# DUE3DOM_MINI_23052016-1301.net
KiCad netlist of a schematic drawn in EAGLE
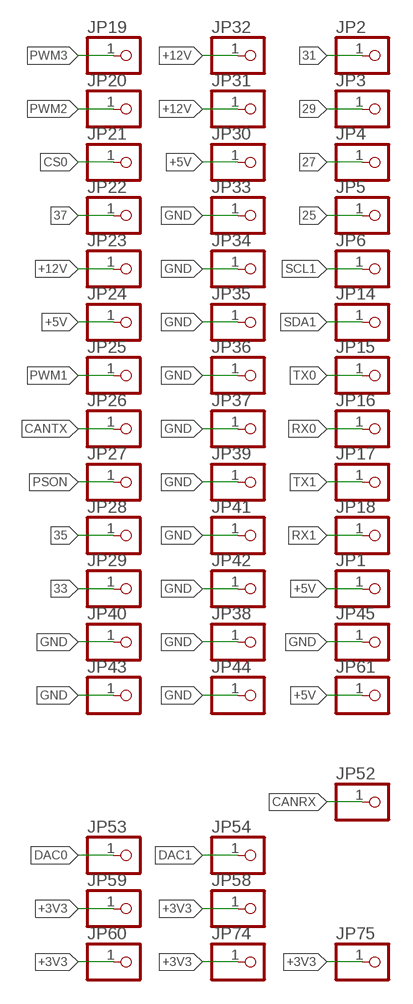
[diagram p0: schematic, sheet 1, part 1 of 3]
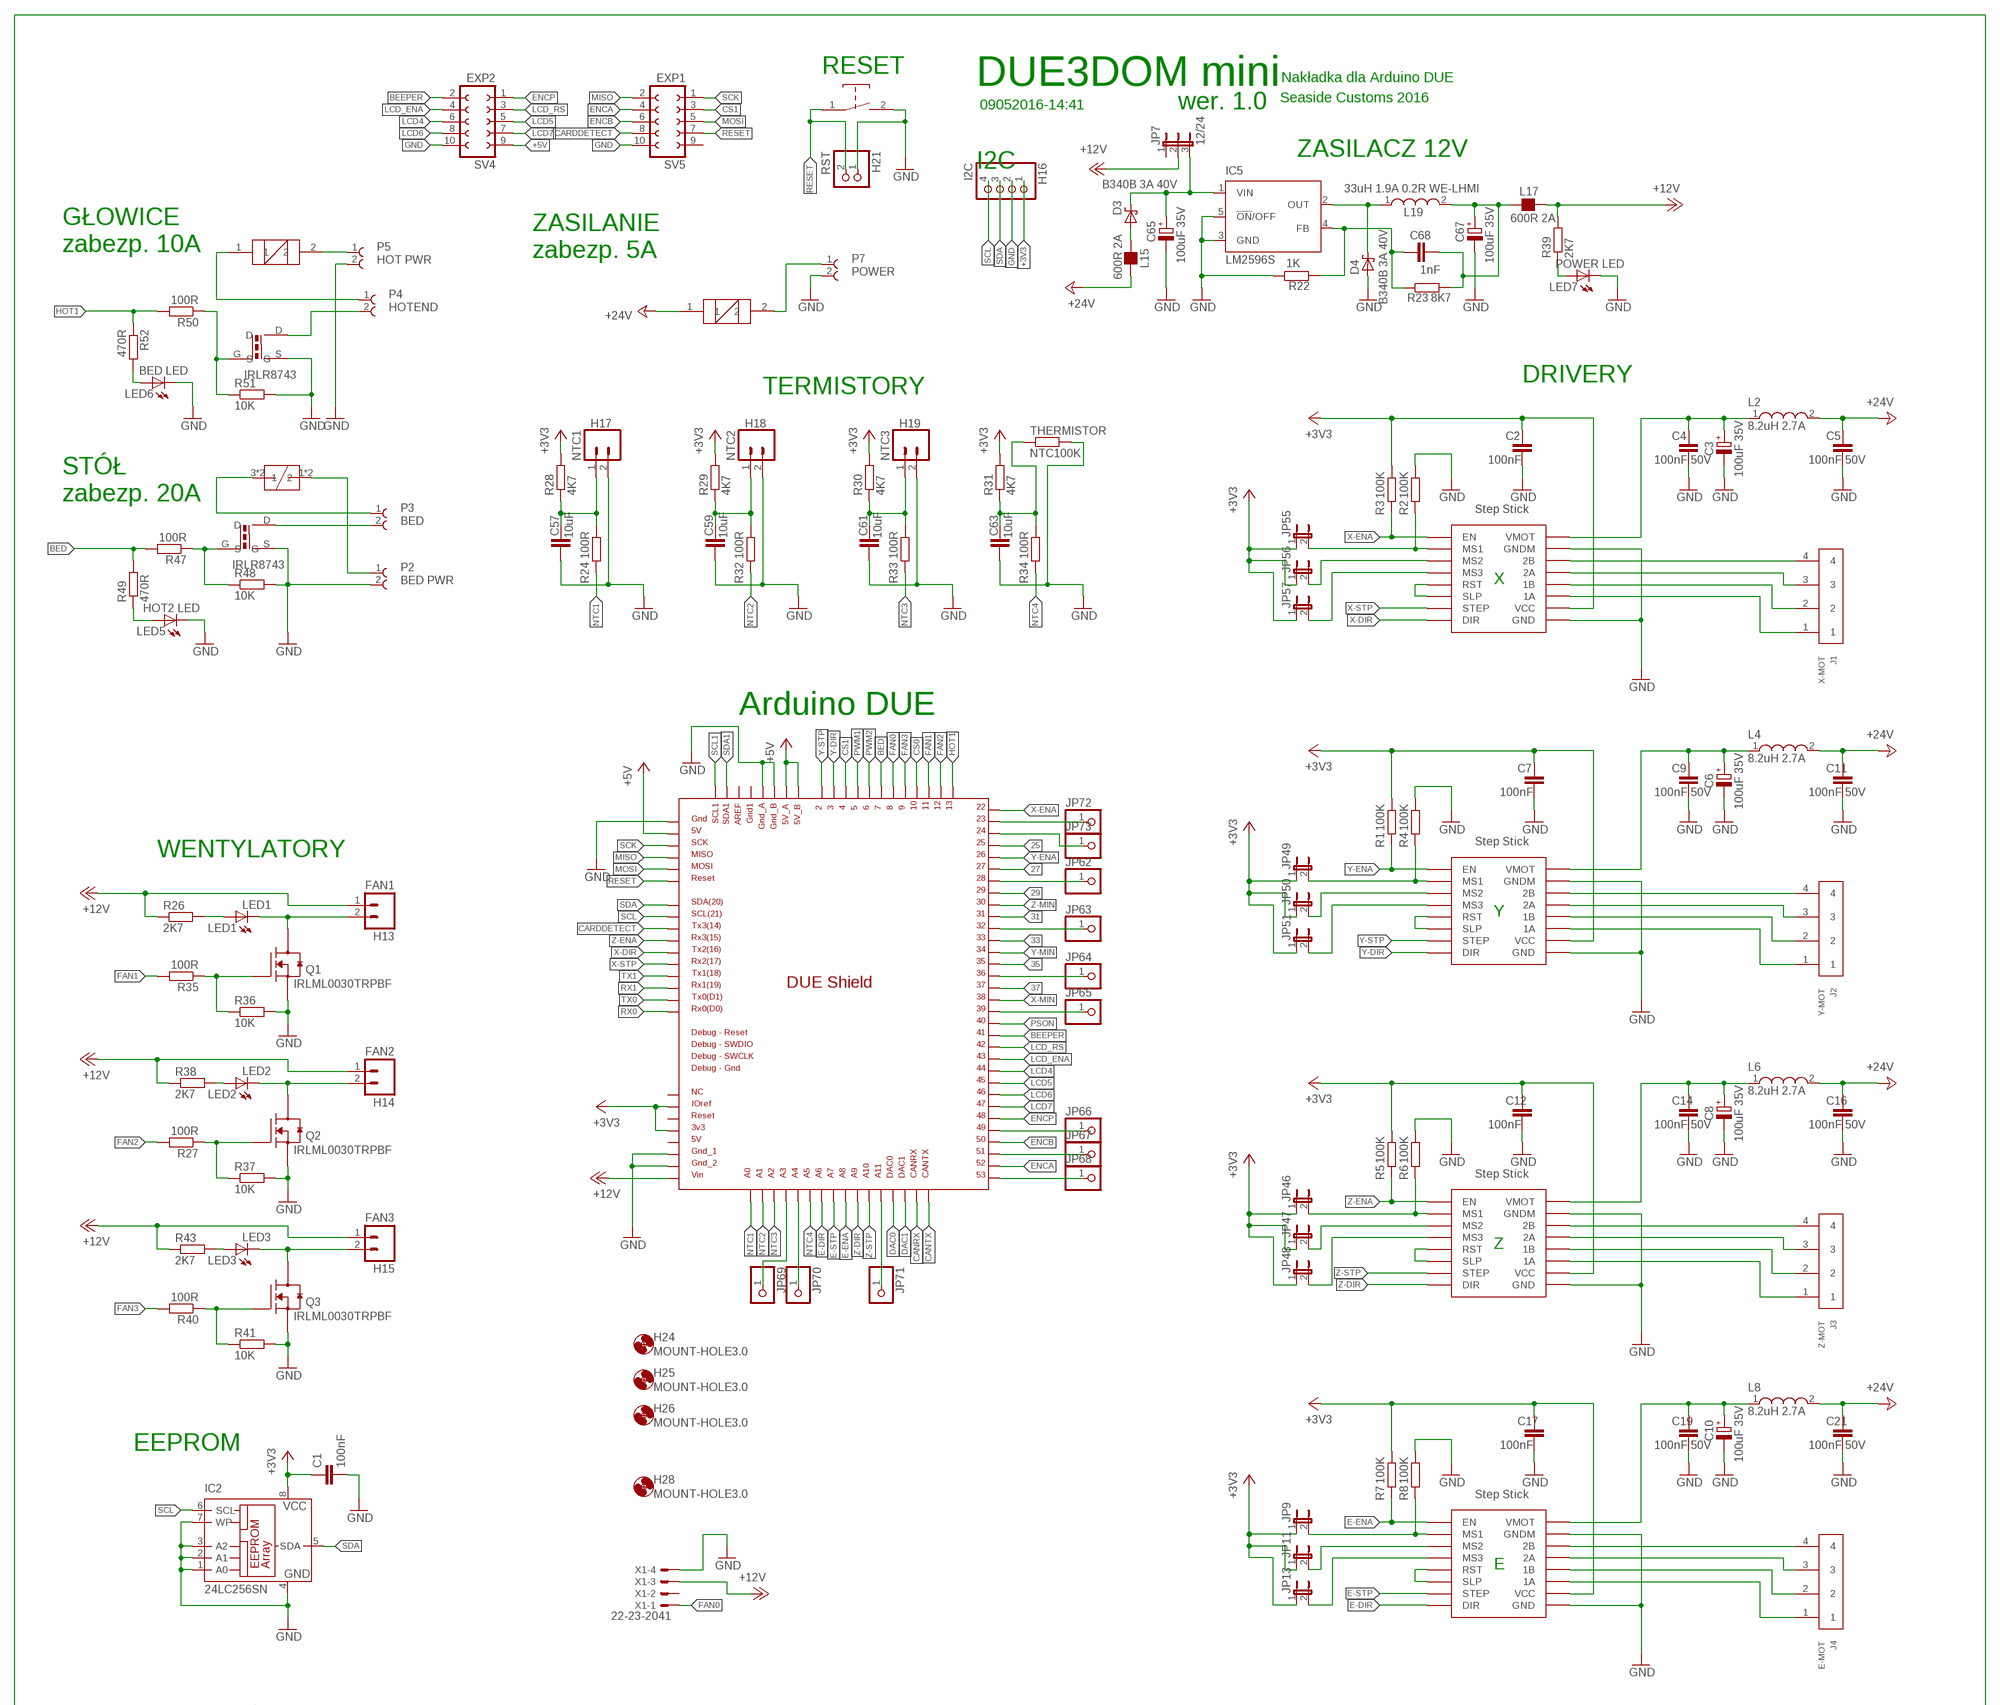
[diagram p1: schematic, sheet 1, part 2 of 3]
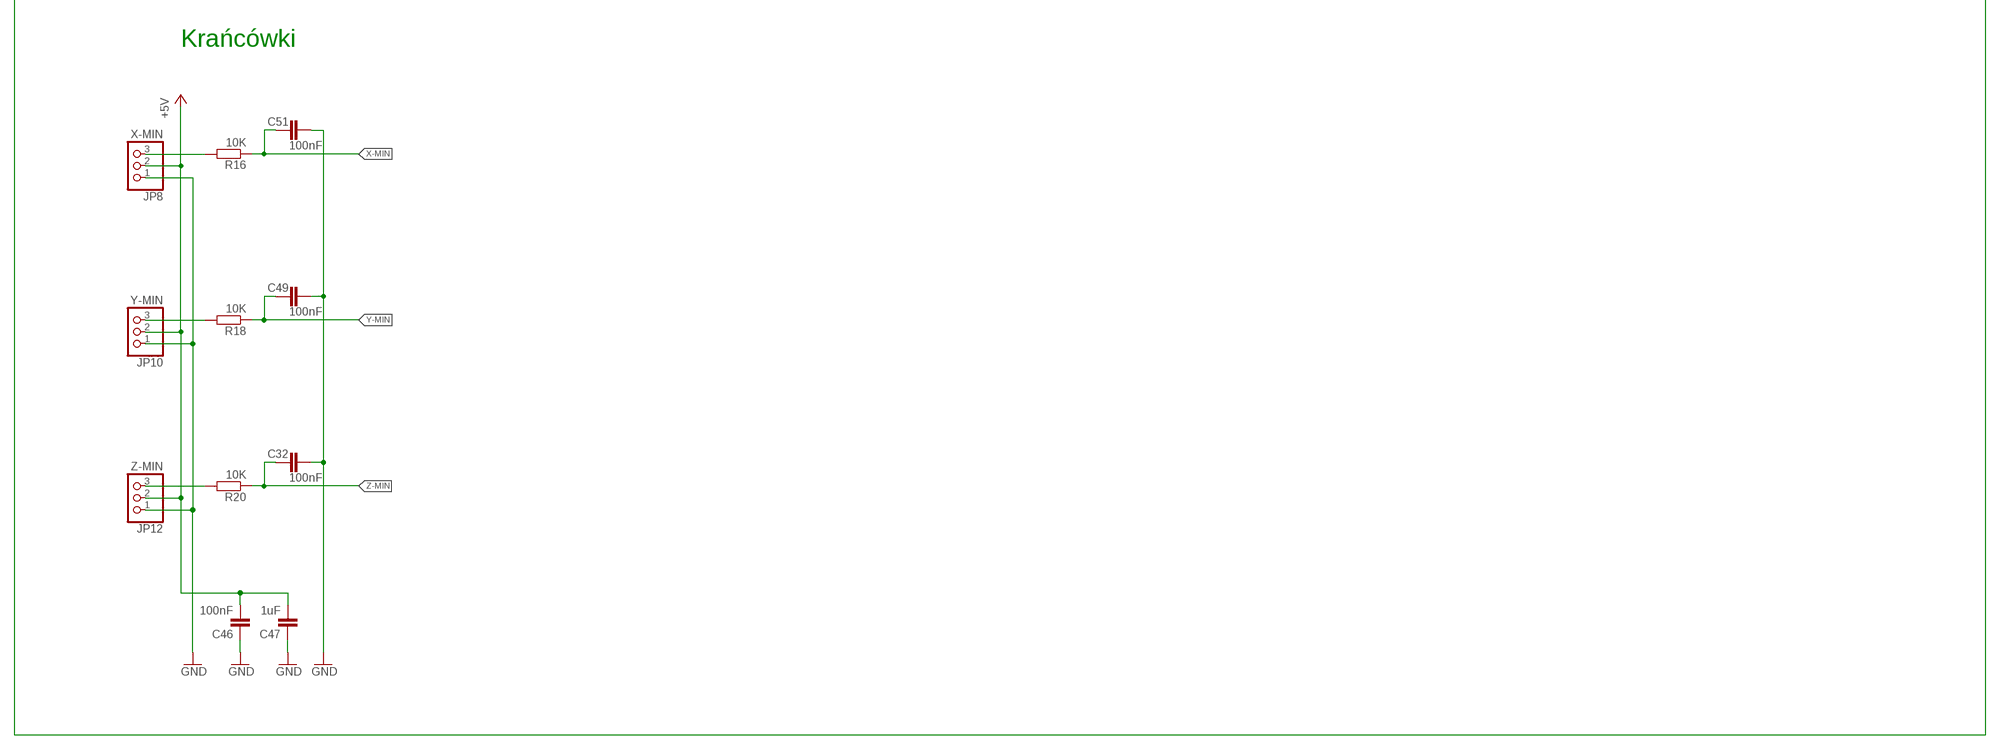
[diagram p2: schematic, sheet 1, part 3 of 3]

(export (version "E")
  (design (tool "Eeschema 10.0.6"))
  (components
    (comp (ref "C1")
      (value "100nF")
      (footprint "eagle-import:C0805")
      (libsource (lib "eagle-import") (part "C-EUC0805"))
    )
    (comp (ref "C2")
      (value "100nF")
      (footprint "eagle-import:C0805")
      (libsource (lib "eagle-import") (part "C-EUC0805"))
    )
    (comp (ref "C3")
      (value "100uF 35V")
      (footprint "eagle-import:E2,5-6")
      (libsource (lib "eagle-import") (part "CPOL-EUE2.5-6"))
    )
    (comp (ref "C4")
      (value "100nF 50V")
      (footprint "eagle-import:C0805")
      (libsource (lib "eagle-import") (part "C-EUC0805"))
    )
    (comp (ref "C5")
      (value "100nF 50V")
      (footprint "eagle-import:C0805")
      (libsource (lib "eagle-import") (part "C-EUC0805"))
    )
    (comp (ref "C6")
      (value "100uF 35V")
      (footprint "eagle-import:E2,5-6")
      (libsource (lib "eagle-import") (part "CPOL-EUE2.5-6"))
    )
    (comp (ref "C7")
      (value "100nF")
      (footprint "eagle-import:C0805")
      (libsource (lib "eagle-import") (part "C-EUC0805"))
    )
    (comp (ref "C8")
      (value "100uF 35V")
      (footprint "eagle-import:E2,5-6")
      (libsource (lib "eagle-import") (part "CPOL-EUE2.5-6"))
    )
    (comp (ref "C9")
      (value "100nF 50V")
      (footprint "eagle-import:C0805")
      (libsource (lib "eagle-import") (part "C-EUC0805"))
    )
    (comp (ref "C10")
      (value "100uF 35V")
      (footprint "eagle-import:E2,5-6")
      (libsource (lib "eagle-import") (part "CPOL-EUE2.5-6"))
    )
    (comp (ref "C11")
      (value "100nF 50V")
      (footprint "eagle-import:C0805")
      (libsource (lib "eagle-import") (part "C-EUC0805"))
    )
    (comp (ref "C12")
      (value "100nF")
      (footprint "eagle-import:C0805")
      (libsource (lib "eagle-import") (part "C-EUC0805"))
    )
    (comp (ref "C14")
      (value "100nF 50V")
      (footprint "eagle-import:C0805")
      (libsource (lib "eagle-import") (part "C-EUC0805"))
    )
    (comp (ref "C16")
      (value "100nF 50V")
      (footprint "eagle-import:C0805")
      (libsource (lib "eagle-import") (part "C-EUC0805"))
    )
    (comp (ref "C17")
      (value "100nF")
      (footprint "eagle-import:C0805")
      (libsource (lib "eagle-import") (part "C-EUC0805"))
    )
    (comp (ref "C19")
      (value "100nF 50V")
      (footprint "eagle-import:C0805")
      (libsource (lib "eagle-import") (part "C-EUC0805"))
    )
    (comp (ref "C21")
      (value "100nF 50V")
      (footprint "eagle-import:C0805")
      (libsource (lib "eagle-import") (part "C-EUC0805"))
    )
    (comp (ref "C32")
      (value "100nF")
      (footprint "eagle-import:C0805")
      (libsource (lib "eagle-import") (part "C-EUC0805"))
    )
    (comp (ref "C46")
      (value "100nF")
      (footprint "eagle-import:C0805")
      (libsource (lib "eagle-import") (part "C-EUC0805"))
    )
    (comp (ref "C47")
      (value "1uF")
      (footprint "eagle-import:C0805")
      (libsource (lib "eagle-import") (part "C-EUC0805"))
    )
    (comp (ref "C49")
      (value "100nF")
      (footprint "eagle-import:C0805")
      (libsource (lib "eagle-import") (part "C-EUC0805"))
    )
    (comp (ref "C51")
      (value "100nF")
      (footprint "eagle-import:C0805")
      (libsource (lib "eagle-import") (part "C-EUC0805"))
    )
    (comp (ref "C57")
      (value "10uF")
      (footprint "eagle-import:C0805")
      (libsource (lib "eagle-import") (part "C-EUC0805"))
    )
    (comp (ref "C59")
      (value "10uF")
      (footprint "eagle-import:C0805")
      (libsource (lib "eagle-import") (part "C-EUC0805"))
    )
    (comp (ref "C61")
      (value "10uF")
      (footprint "eagle-import:C0805")
      (libsource (lib "eagle-import") (part "C-EUC0805"))
    )
    (comp (ref "C63")
      (value "10uF")
      (footprint "eagle-import:C0805")
      (libsource (lib "eagle-import") (part "C-EUC0805"))
    )
    (comp (ref "C65")
      (value "100uF 35V")
      (footprint "eagle-import:E2,5-6")
      (libsource (lib "eagle-import") (part "CPOL-EUE2.5-6"))
    )
    (comp (ref "C67")
      (value "100uF 35V")
      (footprint "eagle-import:E2,5-6")
      (libsource (lib "eagle-import") (part "CPOL-EUE2.5-6"))
    )
    (comp (ref "C68")
      (value "1nF")
      (footprint "eagle-import:C0805")
      (libsource (lib "eagle-import") (part "C-EUC0805"))
    )
    (comp (ref "D3")
      (value "B340B 3A 40V")
      (footprint "eagle-import:SMB")
      (libsource (lib "eagle-import") (part "SCHOTTKY-DIODESMD"))
    )
    (comp (ref "D4")
      (value "B340B 3A 40V")
      (footprint "eagle-import:SMB")
      (libsource (lib "eagle-import") (part "SCHOTTKY-DIODESMD"))
    )
    (comp (ref "FET1")
      (value "DPAK_N-CHANNEL_MOSFET")
      (footprint "eagle-import:DPAK_N-CHANNEL_MOSFET")
      (libsource (lib "eagle-import") (part "DPAK_N-CHANNEL_MOSFET"))
    )
    (comp (ref "FET2")
      (value "DPAK_N-CHANNEL_MOSFET")
      (footprint "eagle-import:DPAK_N-CHANNEL_MOSFET")
      (libsource (lib "eagle-import") (part "DPAK_N-CHANNEL_MOSFET"))
    )
    (comp (ref "H13")
      (value "FAN1")
      (footprint "eagle-import:MOLEX-1X2")
      (libsource (lib "eagle-import") (part "M02POLAR"))
    )
    (comp (ref "H14")
      (value "FAN2")
      (footprint "eagle-import:MOLEX-1X2")
      (libsource (lib "eagle-import") (part "M02POLAR"))
    )
    (comp (ref "H15")
      (value "FAN3")
      (footprint "eagle-import:MOLEX-1X2")
      (libsource (lib "eagle-import") (part "M02POLAR"))
    )
    (comp (ref "H16")
      (value "I2C")
      (footprint "eagle-import:1X04")
      (libsource (lib "eagle-import") (part "PINHD-1X4"))
    )
    (comp (ref "H17")
      (value "NTC1")
      (footprint "eagle-import:MOLEX-1X2")
      (libsource (lib "eagle-import") (part "M02POLAR"))
    )
    (comp (ref "H18")
      (value "NTC2")
      (footprint "eagle-import:MOLEX-1X2")
      (libsource (lib "eagle-import") (part "M02POLAR"))
    )
    (comp (ref "H19")
      (value "NTC3")
      (footprint "eagle-import:MOLEX-1X2")
      (libsource (lib "eagle-import") (part "M02POLAR"))
    )
    (comp (ref "H21")
      (value "RST")
      (footprint "eagle-import:1X02")
      (libsource (lib "eagle-import") (part "PINHD-1X2"))
    )
    (comp (ref "H24")
      (value "MOUNT-HOLE3.0")
      (footprint "eagle-import:3,0")
      (libsource (lib "eagle-import") (part "MOUNT-HOLE3.0"))
    )
    (comp (ref "H25")
      (value "MOUNT-HOLE3.0")
      (footprint "eagle-import:3,0")
      (libsource (lib "eagle-import") (part "MOUNT-HOLE3.0"))
    )
    (comp (ref "H26")
      (value "MOUNT-HOLE3.0")
      (footprint "eagle-import:3,0")
      (libsource (lib "eagle-import") (part "MOUNT-HOLE3.0"))
    )
    (comp (ref "H28")
      (value "MOUNT-HOLE3.0")
      (footprint "eagle-import:3,0")
      (libsource (lib "eagle-import") (part "MOUNT-HOLE3.0"))
    )
    (comp (ref "IC2")
      (value "24LC256SN")
      (footprint "eagle-import:SO-08")
      (fields (field (name "MF") "MICROCHIP") (field (name "MPN") "24LC256-I/SN"))
      (libsource (lib "eagle-import") (part "24SNLC256"))
    )
    (comp (ref "IC5")
      (value "LM2596S")
      (footprint "eagle-import:TO263-5")
      (fields (field (name "MF") "NATIONAL SEMICONDUCTOR") (field (name "MPN") "LM2596S-ADJ/NOPB"))
      (libsource (lib "eagle-import") (part "LM2596S"))
    )
    (comp (ref "J1")
      (value "X-MOT")
      (footprint "eagle-import:66100411622")
      (libsource (lib "eagle-import") (part "66100411622"))
    )
    (comp (ref "J2")
      (value "Y-MOT")
      (footprint "eagle-import:66100411622")
      (libsource (lib "eagle-import") (part "66100411622"))
    )
    (comp (ref "J3")
      (value "Z-MOT")
      (footprint "eagle-import:66100411622")
      (libsource (lib "eagle-import") (part "66100411622"))
    )
    (comp (ref "J4")
      (value "E-MOT")
      (footprint "eagle-import:66100411622")
      (libsource (lib "eagle-import") (part "66100411622"))
    )
    (comp (ref "JP1")
      (value "PINHD-1X1")
      (footprint "eagle-import:1X01")
      (libsource (lib "eagle-import") (part "PINHD-1X1"))
    )
    (comp (ref "JP2")
      (value "PINHD-1X1")
      (footprint "eagle-import:1X01")
      (libsource (lib "eagle-import") (part "PINHD-1X1"))
    )
    (comp (ref "JP3")
      (value "PINHD-1X1")
      (footprint "eagle-import:1X01")
      (libsource (lib "eagle-import") (part "PINHD-1X1"))
    )
    (comp (ref "JP4")
      (value "PINHD-1X1")
      (footprint "eagle-import:1X01")
      (libsource (lib "eagle-import") (part "PINHD-1X1"))
    )
    (comp (ref "JP5")
      (value "PINHD-1X1")
      (footprint "eagle-import:1X01")
      (libsource (lib "eagle-import") (part "PINHD-1X1"))
    )
    (comp (ref "JP6")
      (value "PINHD-1X1")
      (footprint "eagle-import:1X01")
      (libsource (lib "eagle-import") (part "PINHD-1X1"))
    )
    (comp (ref "JP7")
      (value "12/24")
      (footprint "eagle-import:JP2")
      (libsource (lib "eagle-import") (part "JP2E"))
    )
    (comp (ref "JP8")
      (value "X-MIN")
      (footprint "eagle-import:1X03")
      (libsource (lib "eagle-import") (part "PINHD-1X3"))
    )
    (comp (ref "JP9")
      (value "JP1E")
      (footprint "eagle-import:JP1")
      (libsource (lib "eagle-import") (part "JP1E"))
    )
    (comp (ref "JP10")
      (value "Y-MIN")
      (footprint "eagle-import:1X03")
      (libsource (lib "eagle-import") (part "PINHD-1X3"))
    )
    (comp (ref "JP11")
      (value "JP1E")
      (footprint "eagle-import:JP1")
      (libsource (lib "eagle-import") (part "JP1E"))
    )
    (comp (ref "JP12")
      (value "Z-MIN")
      (footprint "eagle-import:1X03")
      (libsource (lib "eagle-import") (part "PINHD-1X3"))
    )
    (comp (ref "JP13")
      (value "JP1E")
      (footprint "eagle-import:JP1")
      (libsource (lib "eagle-import") (part "JP1E"))
    )
    (comp (ref "JP14")
      (value "PINHD-1X1")
      (footprint "eagle-import:1X01")
      (libsource (lib "eagle-import") (part "PINHD-1X1"))
    )
    (comp (ref "JP15")
      (value "PINHD-1X1")
      (footprint "eagle-import:1X01")
      (libsource (lib "eagle-import") (part "PINHD-1X1"))
    )
    (comp (ref "JP16")
      (value "PINHD-1X1")
      (footprint "eagle-import:1X01")
      (libsource (lib "eagle-import") (part "PINHD-1X1"))
    )
    (comp (ref "JP17")
      (value "PINHD-1X1")
      (footprint "eagle-import:1X01")
      (libsource (lib "eagle-import") (part "PINHD-1X1"))
    )
    (comp (ref "JP18")
      (value "PINHD-1X1")
      (footprint "eagle-import:1X01")
      (libsource (lib "eagle-import") (part "PINHD-1X1"))
    )
    (comp (ref "JP19")
      (value "PINHD-1X1")
      (footprint "eagle-import:1X01")
      (libsource (lib "eagle-import") (part "PINHD-1X1"))
    )
    (comp (ref "JP20")
      (value "PINHD-1X1")
      (footprint "eagle-import:1X01")
      (libsource (lib "eagle-import") (part "PINHD-1X1"))
    )
    (comp (ref "JP21")
      (value "PINHD-1X1")
      (footprint "eagle-import:1X01")
      (libsource (lib "eagle-import") (part "PINHD-1X1"))
    )
    (comp (ref "JP22")
      (value "PINHD-1X1")
      (footprint "eagle-import:1X01")
      (libsource (lib "eagle-import") (part "PINHD-1X1"))
    )
    (comp (ref "JP23")
      (value "PINHD-1X1")
      (footprint "eagle-import:1X01")
      (libsource (lib "eagle-import") (part "PINHD-1X1"))
    )
    (comp (ref "JP24")
      (value "PINHD-1X1")
      (footprint "eagle-import:1X01")
      (libsource (lib "eagle-import") (part "PINHD-1X1"))
    )
    (comp (ref "JP25")
      (value "PINHD-1X1")
      (footprint "eagle-import:1X01")
      (libsource (lib "eagle-import") (part "PINHD-1X1"))
    )
    (comp (ref "JP26")
      (value "PINHD-1X1")
      (footprint "eagle-import:1X01")
      (libsource (lib "eagle-import") (part "PINHD-1X1"))
    )
    (comp (ref "JP27")
      (value "PINHD-1X1")
      (footprint "eagle-import:1X01")
      (libsource (lib "eagle-import") (part "PINHD-1X1"))
    )
    (comp (ref "JP28")
      (value "PINHD-1X1")
      (footprint "eagle-import:1X01")
      (libsource (lib "eagle-import") (part "PINHD-1X1"))
    )
    (comp (ref "JP29")
      (value "PINHD-1X1")
      (footprint "eagle-import:1X01")
      (libsource (lib "eagle-import") (part "PINHD-1X1"))
    )
    (comp (ref "JP30")
      (value "PINHD-1X1")
      (footprint "eagle-import:1X01")
      (libsource (lib "eagle-import") (part "PINHD-1X1"))
    )
    (comp (ref "JP31")
      (value "PINHD-1X1")
      (footprint "eagle-import:1X01")
      (libsource (lib "eagle-import") (part "PINHD-1X1"))
    )
    (comp (ref "JP32")
      (value "PINHD-1X1")
      (footprint "eagle-import:1X01")
      (libsource (lib "eagle-import") (part "PINHD-1X1"))
    )
    (comp (ref "JP33")
      (value "PINHD-1X1")
      (footprint "eagle-import:1X01")
      (libsource (lib "eagle-import") (part "PINHD-1X1"))
    )
    (comp (ref "JP34")
      (value "PINHD-1X1")
      (footprint "eagle-import:1X01")
      (libsource (lib "eagle-import") (part "PINHD-1X1"))
    )
    (comp (ref "JP35")
      (value "PINHD-1X1")
      (footprint "eagle-import:1X01")
      (libsource (lib "eagle-import") (part "PINHD-1X1"))
    )
    (comp (ref "JP36")
      (value "PINHD-1X1")
      (footprint "eagle-import:1X01")
      (libsource (lib "eagle-import") (part "PINHD-1X1"))
    )
    (comp (ref "JP37")
      (value "PINHD-1X1")
      (footprint "eagle-import:1X01")
      (libsource (lib "eagle-import") (part "PINHD-1X1"))
    )
    (comp (ref "JP38")
      (value "PINHD-1X1")
      (footprint "eagle-import:1X01")
      (libsource (lib "eagle-import") (part "PINHD-1X1"))
    )
    (comp (ref "JP39")
      (value "PINHD-1X1")
      (footprint "eagle-import:1X01")
      (libsource (lib "eagle-import") (part "PINHD-1X1"))
    )
    (comp (ref "JP40")
      (value "PINHD-1X1")
      (footprint "eagle-import:1X01")
      (libsource (lib "eagle-import") (part "PINHD-1X1"))
    )
    (comp (ref "JP41")
      (value "PINHD-1X1")
      (footprint "eagle-import:1X01")
      (libsource (lib "eagle-import") (part "PINHD-1X1"))
    )
    (comp (ref "JP42")
      (value "PINHD-1X1")
      (footprint "eagle-import:1X01")
      (libsource (lib "eagle-import") (part "PINHD-1X1"))
    )
    (comp (ref "JP43")
      (value "PINHD-1X1")
      (footprint "eagle-import:1X01")
      (libsource (lib "eagle-import") (part "PINHD-1X1"))
    )
    (comp (ref "JP44")
      (value "PINHD-1X1")
      (footprint "eagle-import:1X01")
      (libsource (lib "eagle-import") (part "PINHD-1X1"))
    )
    (comp (ref "JP45")
      (value "PINHD-1X1")
      (footprint "eagle-import:1X01")
      (libsource (lib "eagle-import") (part "PINHD-1X1"))
    )
    (comp (ref "JP46")
      (value "JP1E")
      (footprint "eagle-import:JP1")
      (libsource (lib "eagle-import") (part "JP1E"))
    )
    (comp (ref "JP47")
      (value "JP1E")
      (footprint "eagle-import:JP1")
      (libsource (lib "eagle-import") (part "JP1E"))
    )
    (comp (ref "JP48")
      (value "JP1E")
      (footprint "eagle-import:JP1")
      (libsource (lib "eagle-import") (part "JP1E"))
    )
    (comp (ref "JP49")
      (value "JP1E")
      (footprint "eagle-import:JP1")
      (libsource (lib "eagle-import") (part "JP1E"))
    )
    (comp (ref "JP50")
      (value "JP1E")
      (footprint "eagle-import:JP1")
      (libsource (lib "eagle-import") (part "JP1E"))
    )
    (comp (ref "JP51")
      (value "JP1E")
      (footprint "eagle-import:JP1")
      (libsource (lib "eagle-import") (part "JP1E"))
    )
    (comp (ref "JP52")
      (value "PINHD-1X1")
      (footprint "eagle-import:1X01")
      (libsource (lib "eagle-import") (part "PINHD-1X1"))
    )
    (comp (ref "JP53")
      (value "PINHD-1X1")
      (footprint "eagle-import:1X01")
      (libsource (lib "eagle-import") (part "PINHD-1X1"))
    )
    (comp (ref "JP54")
      (value "PINHD-1X1")
      (footprint "eagle-import:1X01")
      (libsource (lib "eagle-import") (part "PINHD-1X1"))
    )
    (comp (ref "JP55")
      (value "JP1E")
      (footprint "eagle-import:JP1")
      (libsource (lib "eagle-import") (part "JP1E"))
    )
    (comp (ref "JP56")
      (value "JP1E")
      (footprint "eagle-import:JP1")
      (libsource (lib "eagle-import") (part "JP1E"))
    )
    (comp (ref "JP57")
      (value "JP1E")
      (footprint "eagle-import:JP1")
      (libsource (lib "eagle-import") (part "JP1E"))
    )
    (comp (ref "JP58")
      (value "PINHD-1X1")
      (footprint "eagle-import:1X01")
      (libsource (lib "eagle-import") (part "PINHD-1X1"))
    )
    (comp (ref "JP59")
      (value "PINHD-1X1")
      (footprint "eagle-import:1X01")
      (libsource (lib "eagle-import") (part "PINHD-1X1"))
    )
    (comp (ref "JP60")
      (value "PINHD-1X1")
      (footprint "eagle-import:1X01")
      (libsource (lib "eagle-import") (part "PINHD-1X1"))
    )
    (comp (ref "JP61")
      (value "PINHD-1X1")
      (footprint "eagle-import:1X01")
      (libsource (lib "eagle-import") (part "PINHD-1X1"))
    )
    (comp (ref "JP62")
      (value "PINHD-1X1")
      (footprint "eagle-import:1X01")
      (libsource (lib "eagle-import") (part "PINHD-1X1"))
    )
    (comp (ref "JP63")
      (value "PINHD-1X1")
      (footprint "eagle-import:1X01")
      (libsource (lib "eagle-import") (part "PINHD-1X1"))
    )
    (comp (ref "JP64")
      (value "PINHD-1X1")
      (footprint "eagle-import:1X01")
      (libsource (lib "eagle-import") (part "PINHD-1X1"))
    )
    (comp (ref "JP65")
      (value "PINHD-1X1")
      (footprint "eagle-import:1X01")
      (libsource (lib "eagle-import") (part "PINHD-1X1"))
    )
    (comp (ref "JP66")
      (value "PINHD-1X1")
      (footprint "eagle-import:1X01")
      (libsource (lib "eagle-import") (part "PINHD-1X1"))
    )
    (comp (ref "JP67")
      (value "PINHD-1X1")
      (footprint "eagle-import:1X01")
      (libsource (lib "eagle-import") (part "PINHD-1X1"))
    )
    (comp (ref "JP68")
      (value "PINHD-1X1")
      (footprint "eagle-import:1X01")
      (libsource (lib "eagle-import") (part "PINHD-1X1"))
    )
    (comp (ref "JP69")
      (value "PINHD-1X1")
      (footprint "eagle-import:1X01")
      (libsource (lib "eagle-import") (part "PINHD-1X1"))
    )
    (comp (ref "JP70")
      (value "PINHD-1X1")
      (footprint "eagle-import:1X01")
      (libsource (lib "eagle-import") (part "PINHD-1X1"))
    )
    (comp (ref "JP71")
      (value "PINHD-1X1")
      (footprint "eagle-import:1X01")
      (libsource (lib "eagle-import") (part "PINHD-1X1"))
    )
    (comp (ref "JP72")
      (value "PINHD-1X1")
      (footprint "eagle-import:1X01")
      (libsource (lib "eagle-import") (part "PINHD-1X1"))
    )
    (comp (ref "JP73")
      (value "PINHD-1X1")
      (footprint "eagle-import:1X01")
      (libsource (lib "eagle-import") (part "PINHD-1X1"))
    )
    (comp (ref "JP74")
      (value "PINHD-1X1")
      (footprint "eagle-import:1X01")
      (libsource (lib "eagle-import") (part "PINHD-1X1"))
    )
    (comp (ref "JP75")
      (value "PINHD-1X1")
      (footprint "eagle-import:1X01")
      (libsource (lib "eagle-import") (part "PINHD-1X1"))
    )
    (comp (ref "L2")
      (value "8.2uH 2.7A")
      (footprint "eagle-import:WE-PD_7332_7345_PLASTIC_BASE")
      (libsource (lib "eagle-import") (part "WE-PD_7332/7345_PLASTIC_BASE"))
    )
    (comp (ref "L4")
      (value "8.2uH 2.7A")
      (footprint "eagle-import:WE-PD_7332_7345_PLASTIC_BASE")
      (libsource (lib "eagle-import") (part "WE-PD_7332/7345_PLASTIC_BASE"))
    )
    (comp (ref "L6")
      (value "8.2uH 2.7A")
      (footprint "eagle-import:WE-PD_7332_7345_PLASTIC_BASE")
      (libsource (lib "eagle-import") (part "WE-PD_7332/7345_PLASTIC_BASE"))
    )
    (comp (ref "L8")
      (value "8.2uH 2.7A")
      (footprint "eagle-import:WE-PD_7332_7345_PLASTIC_BASE")
      (libsource (lib "eagle-import") (part "WE-PD_7332/7345_PLASTIC_BASE"))
    )
    (comp (ref "L15")
      (value "600R 2A")
      (footprint "eagle-import:L1206")
      (libsource (lib "eagle-import") (part "FB_1206"))
    )
    (comp (ref "L17")
      (value "600R 2A")
      (footprint "eagle-import:L1206")
      (libsource (lib "eagle-import") (part "FB_1206"))
    )
    (comp (ref "L19")
      (value "33uH 1.9A 0.2R WE-LHMI")
      (footprint "eagle-import:WE-LHMI_7030_7050")
      (libsource (lib "eagle-import") (part "WE-LHMI_7030/7050"))
    )
    (comp (ref "LED1")
      (value "LED1")
      (footprint "eagle-import:LED_0805_BIVAR_VLP-250-F")
      (libsource (lib "eagle-import") (part "LED_0805_BIVAR_VLP-250-F"))
    )
    (comp (ref "LED2")
      (value "LED2")
      (footprint "eagle-import:LED_0805_BIVAR_VLP-250-F")
      (libsource (lib "eagle-import") (part "LED_0805_BIVAR_VLP-250-F"))
    )
    (comp (ref "LED3")
      (value "LED3")
      (footprint "eagle-import:LED_0805_BIVAR_VLP-250-F")
      (libsource (lib "eagle-import") (part "LED_0805_BIVAR_VLP-250-F"))
    )
    (comp (ref "LED5")
      (value "HOT2 LED")
      (footprint "eagle-import:LED_0805_BIVAR_VLP-250-F")
      (libsource (lib "eagle-import") (part "LED_0805_BIVAR_VLP-250-F"))
    )
    (comp (ref "LED6")
      (value "BED LED")
      (footprint "eagle-import:LED_0805_BIVAR_VLP-250-F")
      (libsource (lib "eagle-import") (part "LED_0805_BIVAR_VLP-250-F"))
    )
    (comp (ref "LED7")
      (value "POWER LED")
      (footprint "eagle-import:LED_0805_BIVAR_VLP-250-F")
      (libsource (lib "eagle-import") (part "LED_0805_BIVAR_VLP-250-F"))
    )
    (comp (ref "P2")
      (value "BED PWR")
      (footprint "eagle-import:691241710002")
      (libsource (lib "eagle-import") (part "691241710002"))
    )
    (comp (ref "P3")
      (value "BED")
      (footprint "eagle-import:691241710002")
      (libsource (lib "eagle-import") (part "691241710002"))
    )
    (comp (ref "P4")
      (value "HOTEND")
      (footprint "eagle-import:691241710002")
      (libsource (lib "eagle-import") (part "691241710002"))
    )
    (comp (ref "P5")
      (value "HOT PWR")
      (footprint "eagle-import:691241710002")
      (libsource (lib "eagle-import") (part "691241710002"))
    )
    (comp (ref "P7")
      (value "POWER")
      (footprint "eagle-import:691241710002")
      (libsource (lib "eagle-import") (part "691241710002"))
    )
    (comp (ref "Q1")
      (value "IRLML0030TRPBF")
      (footprint "eagle-import:SOT95P280X135-3N")
      (libsource (lib "eagle-import") (part "MOSFET-NCH_SOT-23"))
    )
    (comp (ref "Q2")
      (value "IRLML0030TRPBF")
      (footprint "eagle-import:SOT95P280X135-3N")
      (libsource (lib "eagle-import") (part "MOSFET-NCH_SOT-23"))
    )
    (comp (ref "Q3")
      (value "IRLML0030TRPBF")
      (footprint "eagle-import:SOT95P280X135-3N")
      (libsource (lib "eagle-import") (part "MOSFET-NCH_SOT-23"))
    )
    (comp (ref "R1")
      (value "100K")
      (footprint "eagle-import:R0805")
      (libsource (lib "eagle-import") (part "R-EU_R0805"))
    )
    (comp (ref "R2")
      (value "100K")
      (footprint "eagle-import:R0805")
      (libsource (lib "eagle-import") (part "R-EU_R0805"))
    )
    (comp (ref "R3")
      (value "100K")
      (footprint "eagle-import:R0805")
      (libsource (lib "eagle-import") (part "R-EU_R0805"))
    )
    (comp (ref "R4")
      (value "100K")
      (footprint "eagle-import:R0805")
      (libsource (lib "eagle-import") (part "R-EU_R0805"))
    )
    (comp (ref "R5")
      (value "100K")
      (footprint "eagle-import:R0805")
      (libsource (lib "eagle-import") (part "R-EU_R0805"))
    )
    (comp (ref "R6")
      (value "100K")
      (footprint "eagle-import:R0805")
      (libsource (lib "eagle-import") (part "R-EU_R0805"))
    )
    (comp (ref "R7")
      (value "100K")
      (footprint "eagle-import:R0805")
      (libsource (lib "eagle-import") (part "R-EU_R0805"))
    )
    (comp (ref "R8")
      (value "100K")
      (footprint "eagle-import:R0805")
      (libsource (lib "eagle-import") (part "R-EU_R0805"))
    )
    (comp (ref "R16")
      (value "10K")
      (footprint "eagle-import:R0805")
      (libsource (lib "eagle-import") (part "R-EU_R0805"))
    )
    (comp (ref "R18")
      (value "10K")
      (footprint "eagle-import:R0805")
      (libsource (lib "eagle-import") (part "R-EU_R0805"))
    )
    (comp (ref "R20")
      (value "10K")
      (footprint "eagle-import:R0805")
      (libsource (lib "eagle-import") (part "R-EU_R0805"))
    )
    (comp (ref "R22")
      (value "1K")
      (footprint "eagle-import:R0805")
      (libsource (lib "eagle-import") (part "R-EU_R0805"))
    )
    (comp (ref "R23")
      (value "8K7")
      (footprint "eagle-import:R0805")
      (libsource (lib "eagle-import") (part "R-EU_R0805"))
    )
    (comp (ref "R24")
      (value "100R")
      (footprint "eagle-import:R0805")
      (libsource (lib "eagle-import") (part "R-EU_R0805"))
    )
    (comp (ref "R26")
      (value "2K7")
      (footprint "eagle-import:R0805")
      (libsource (lib "eagle-import") (part "R-EU_R0805"))
    )
    (comp (ref "R27")
      (value "100R")
      (footprint "eagle-import:R0805")
      (libsource (lib "eagle-import") (part "R-EU_R0805"))
    )
    (comp (ref "R28")
      (value "4K7")
      (footprint "eagle-import:R0805")
      (libsource (lib "eagle-import") (part "R-EU_R0805"))
    )
    (comp (ref "R29")
      (value "4K7")
      (footprint "eagle-import:R0805")
      (libsource (lib "eagle-import") (part "R-EU_R0805"))
    )
    (comp (ref "R30")
      (value "4K7")
      (footprint "eagle-import:R0805")
      (libsource (lib "eagle-import") (part "R-EU_R0805"))
    )
    (comp (ref "R31")
      (value "4K7")
      (footprint "eagle-import:R0805")
      (libsource (lib "eagle-import") (part "R-EU_R0805"))
    )
    (comp (ref "R32")
      (value "100R")
      (footprint "eagle-import:R0805")
      (libsource (lib "eagle-import") (part "R-EU_R0805"))
    )
    (comp (ref "R33")
      (value "100R")
      (footprint "eagle-import:R0805")
      (libsource (lib "eagle-import") (part "R-EU_R0805"))
    )
    (comp (ref "R34")
      (value "100R")
      (footprint "eagle-import:R0805")
      (libsource (lib "eagle-import") (part "R-EU_R0805"))
    )
    (comp (ref "R35")
      (value "100R")
      (footprint "eagle-import:R0805")
      (libsource (lib "eagle-import") (part "R-EU_R0805"))
    )
    (comp (ref "R36")
      (value "10K")
      (footprint "eagle-import:R0805")
      (libsource (lib "eagle-import") (part "R-EU_R0805"))
    )
    (comp (ref "R37")
      (value "10K")
      (footprint "eagle-import:R0805")
      (libsource (lib "eagle-import") (part "R-EU_R0805"))
    )
    (comp (ref "R38")
      (value "2K7")
      (footprint "eagle-import:R0805")
      (libsource (lib "eagle-import") (part "R-EU_R0805"))
    )
    (comp (ref "R39")
      (value "2K7")
      (footprint "eagle-import:R0805")
      (libsource (lib "eagle-import") (part "R-EU_R0805"))
    )
    (comp (ref "R40")
      (value "100R")
      (footprint "eagle-import:R0805")
      (libsource (lib "eagle-import") (part "R-EU_R0805"))
    )
    (comp (ref "R41")
      (value "10K")
      (footprint "eagle-import:R0805")
      (libsource (lib "eagle-import") (part "R-EU_R0805"))
    )
    (comp (ref "R43")
      (value "2K7")
      (footprint "eagle-import:R0805")
      (libsource (lib "eagle-import") (part "R-EU_R0805"))
    )
    (comp (ref "R47")
      (value "100R")
      (footprint "eagle-import:R0805")
      (libsource (lib "eagle-import") (part "R-EU_R0805"))
    )
    (comp (ref "R48")
      (value "10K")
      (footprint "eagle-import:R0805")
      (libsource (lib "eagle-import") (part "R-EU_R0805"))
    )
    (comp (ref "R49")
      (value "470R")
      (footprint "eagle-import:R0805")
      (libsource (lib "eagle-import") (part "R-EU_R0805"))
    )
    (comp (ref "R50")
      (value "100R")
      (footprint "eagle-import:R0805")
      (libsource (lib "eagle-import") (part "R-EU_R0805"))
    )
    (comp (ref "R51")
      (value "10K")
      (footprint "eagle-import:R0805")
      (libsource (lib "eagle-import") (part "R-EU_R0805"))
    )
    (comp (ref "R52")
      (value "470R")
      (footprint "eagle-import:R0805")
      (libsource (lib "eagle-import") (part "R-EU_R0805"))
    )
    (comp (ref "RESET")
      (value "RESET")
      (footprint "eagle-import:WIDE_TACT")
      (libsource (lib "eagle-import") (part "WIDE_TACT"))
    )
    (comp (ref "STEPSTICK-X")
      (value "STEP-STICK")
      (footprint "eagle-import:STEP-STICK")
      (libsource (lib "eagle-import") (part "STEP-STICK"))
    )
    (comp (ref "STEPSTICK-Y")
      (value "STEP-STICK")
      (footprint "eagle-import:STEP-STICK")
      (libsource (lib "eagle-import") (part "STEP-STICK"))
    )
    (comp (ref "STEPSTICK-Z1")
      (value "STEP-STICK")
      (footprint "eagle-import:STEP-STICK")
      (libsource (lib "eagle-import") (part "STEP-STICK"))
    )
    (comp (ref "STEPSTICK-Z2")
      (value "STEP-STICK")
      (footprint "eagle-import:STEP-STICK")
      (libsource (lib "eagle-import") (part "STEP-STICK"))
    )
    (comp (ref "SV4")
      (value "EXP2")
      (footprint "eagle-import:FE05-2")
      (libsource (lib "eagle-import") (part "FE05-2"))
    )
    (comp (ref "SV5")
      (value "EXP1")
      (footprint "eagle-import:FE05-2")
      (libsource (lib "eagle-import") (part "FE05-2"))
    )
    (comp (ref "THERMISTOR")
      (value "NTC100K")
      (footprint "eagle-import:M1206")
      (libsource (lib "eagle-import") (part "R-EU_M1206"))
    )
    (comp (ref "U$1")
      (value "DUE(NORMAL)")
      (footprint "eagle-import:DUE(NORMAL)")
      (libsource (lib "eagle-import") (part "DUE(NORMAL)"))
    )
    (comp (ref "U$2")
      (value "FUSE_1808")
      (footprint "eagle-import:FUSE_1808")
      (libsource (lib "eagle-import") (part "FUSE_1808"))
    )
    (comp (ref "U$3")
      (value "FUSE_1808")
      (footprint "eagle-import:FUSE_1808")
      (libsource (lib "eagle-import") (part "FUSE_1808"))
    )
    (comp (ref "U$13")
      (value "KEYSTONE_3568")
      (footprint "eagle-import:KEYSTONE_3568")
      (libsource (lib "eagle-import") (part "KEYSTONE_3568"))
    )
    (comp (ref "X1")
      (value "22-23-2041")
      (footprint "eagle-import:22-23-2041")
      (fields (field (name "MF") "MOLEX"))
      (libsource (lib "eagle-import") (part "22-23-2041"))
    )
  )
  (nets
    (net (code "1") (name "+3V3") (class "Default")
      (node (ref "C1") (pin "1") (pinfunction "1_1") (pintype "passive"))
      (node (ref "C12") (pin "1") (pinfunction "1_1") (pintype "passive"))
      (node (ref "C17") (pin "1") (pinfunction "1_1") (pintype "passive"))
      (node (ref "C2") (pin "1") (pinfunction "1_1") (pintype "passive"))
      (node (ref "C7") (pin "1") (pinfunction "1_1") (pintype "passive"))
      (node (ref "H16") (pin "1") (pinfunction "1_1") (pintype "passive"))
      (node (ref "IC2") (pin "8") (pinfunction "VCC_8") (pintype "power_in"))
      (node (ref "JP11") (pin "1") (pinfunction "1_1") (pintype "passive"))
      (node (ref "JP13") (pin "1") (pinfunction "1_1") (pintype "passive"))
      (node (ref "JP46") (pin "1") (pinfunction "1_1") (pintype "passive"))
      (node (ref "JP47") (pin "1") (pinfunction "1_1") (pintype "passive"))
      (node (ref "JP48") (pin "1") (pinfunction "1_1") (pintype "passive"))
      (node (ref "JP49") (pin "1") (pinfunction "1_1") (pintype "passive"))
      (node (ref "JP50") (pin "1") (pinfunction "1_1") (pintype "passive"))
      (node (ref "JP51") (pin "1") (pinfunction "1_1") (pintype "passive"))
      (node (ref "JP55") (pin "1") (pinfunction "1_1") (pintype "passive"))
      (node (ref "JP56") (pin "1") (pinfunction "1_1") (pintype "passive"))
      (node (ref "JP57") (pin "1") (pinfunction "1_1") (pintype "passive"))
      (node (ref "JP58") (pin "1") (pinfunction "1_1") (pintype "passive"))
      (node (ref "JP59") (pin "1") (pinfunction "1_1") (pintype "passive"))
      (node (ref "JP60") (pin "1") (pinfunction "1_1") (pintype "passive"))
      (node (ref "JP74") (pin "1") (pinfunction "1_1") (pintype "passive"))
      (node (ref "JP75") (pin "1") (pinfunction "1_1") (pintype "passive"))
      (node (ref "JP9") (pin "1") (pinfunction "1_1") (pintype "passive"))
      (node (ref "R1") (pin "1") (pinfunction "1_1") (pintype "passive"))
      (node (ref "R28") (pin "2") (pinfunction "2_2") (pintype "passive"))
      (node (ref "R29") (pin "2") (pinfunction "2_2") (pintype "passive"))
      (node (ref "R3") (pin "1") (pinfunction "1_1") (pintype "passive"))
      (node (ref "R30") (pin "2") (pinfunction "2_2") (pintype "passive"))
      (node (ref "R31") (pin "2") (pinfunction "2_2") (pintype "passive"))
      (node (ref "R5") (pin "1") (pinfunction "1_1") (pintype "passive"))
      (node (ref "R7") (pin "1") (pinfunction "1_1") (pintype "passive"))
      (node (ref "STEPSTICK-X") (pin "VDD") (pinfunction "VCC_VDD") (pintype "bidirectional"))
      (node (ref "STEPSTICK-Y") (pin "VDD") (pinfunction "VCC_VDD") (pintype "bidirectional"))
      (node (ref "STEPSTICK-Z1") (pin "VDD") (pinfunction "VCC_VDD") (pintype "bidirectional"))
      (node (ref "STEPSTICK-Z2") (pin "VDD") (pinfunction "VCC_VDD") (pintype "bidirectional"))
      (node (ref "U$1") (pin "3V3") (pinfunction "3V3_3V3") (pintype "bidirectional"))
      (node (ref "U$1") (pin "IOREF") (pinfunction "IOREF_IOREF") (pintype "bidirectional"))
    )
    (net (code "2") (name "+5V") (class "Default")
      (node (ref "C46") (pin "2") (pinfunction "2_2") (pintype "passive"))
      (node (ref "C47") (pin "2") (pinfunction "2_2") (pintype "passive"))
      (node (ref "JP1") (pin "1") (pinfunction "1_1") (pintype "passive"))
      (node (ref "JP10") (pin "2") (pinfunction "2_2") (pintype "passive"))
      (node (ref "JP12") (pin "2") (pinfunction "2_2") (pintype "passive"))
      (node (ref "JP24") (pin "1") (pinfunction "1_1") (pintype "passive"))
      (node (ref "JP30") (pin "1") (pinfunction "1_1") (pintype "passive"))
      (node (ref "JP61") (pin "1") (pinfunction "1_1") (pintype "passive"))
      (node (ref "JP8") (pin "2") (pinfunction "2_2") (pintype "passive"))
      (node (ref "SV4") (pin "9") (pinfunction "9_9") (pintype "passive"))
      (node (ref "U$1") (pin "5V_A") (pinfunction "5V_A_5V_A") (pintype "bidirectional"))
      (node (ref "U$1") (pin "5V_B") (pinfunction "5V_B_5V_B") (pintype "bidirectional"))
      (node (ref "U$1") (pin "GND_ICSP") (pinfunction "GND_ICSP_GND_ICSP") (pintype "bidirectional"))
    )
    (net (code "3") (name "+12V") (class "Default")
      (node (ref "H13") (pin "1") (pinfunction "1_1") (pintype "passive"))
      (node (ref "H14") (pin "1") (pinfunction "1_1") (pintype "passive"))
      (node (ref "H15") (pin "1") (pinfunction "1_1") (pintype "passive"))
      (node (ref "JP23") (pin "1") (pinfunction "1_1") (pintype "passive"))
      (node (ref "JP31") (pin "1") (pinfunction "1_1") (pintype "passive"))
      (node (ref "JP32") (pin "1") (pinfunction "1_1") (pintype "passive"))
      (node (ref "JP7") (pin "2") (pinfunction "2_2") (pintype "passive"))
      (node (ref "L17") (pin "2") (pinfunction "2_2") (pintype "passive"))
      (node (ref "R26") (pin "1") (pinfunction "1_1") (pintype "passive"))
      (node (ref "R38") (pin "1") (pinfunction "1_1") (pintype "passive"))
      (node (ref "R39") (pin "2") (pinfunction "2_2") (pintype "passive"))
      (node (ref "R43") (pin "1") (pinfunction "1_1") (pintype "passive"))
      (node (ref "U$1") (pin "VIN") (pinfunction "VIN_VIN") (pintype "bidirectional"))
      (node (ref "X1") (pin "3") (pinfunction "S_3") (pintype "passive"))
    )
    (net (code "4") (name "+24V") (class "Default")
      (node (ref "C11") (pin "1") (pinfunction "1_1") (pintype "passive"))
      (node (ref "C16") (pin "1") (pinfunction "1_1") (pintype "passive"))
      (node (ref "C21") (pin "1") (pinfunction "1_1") (pintype "passive"))
      (node (ref "C5") (pin "1") (pinfunction "1_1") (pintype "passive"))
      (node (ref "L15") (pin "1") (pinfunction "1_1") (pintype "passive"))
      (node (ref "L2") (pin "2") (pinfunction "2_2") (pintype "passive"))
      (node (ref "L4") (pin "2") (pinfunction "2_2") (pintype "passive"))
      (node (ref "L6") (pin "2") (pinfunction "2_2") (pintype "passive"))
      (node (ref "L8") (pin "2") (pinfunction "2_2") (pintype "passive"))
      (node (ref "U$3") (pin "1") (pinfunction "1_1") (pintype "bidirectional"))
    )
    (net (code "5") (name "25") (class "Default")
      (node (ref "JP5") (pin "1") (pinfunction "1_1") (pintype "passive"))
      (node (ref "U$1") (pin "25") (pinfunction "25_25") (pintype "bidirectional"))
    )
    (net (code "6") (name "27") (class "Default")
      (node (ref "JP4") (pin "1") (pinfunction "1_1") (pintype "passive"))
      (node (ref "U$1") (pin "27") (pinfunction "27_27") (pintype "bidirectional"))
    )
    (net (code "7") (name "29") (class "Default")
      (node (ref "JP3") (pin "1") (pinfunction "1_1") (pintype "passive"))
      (node (ref "U$1") (pin "29") (pinfunction "29_29") (pintype "bidirectional"))
    )
    (net (code "8") (name "31") (class "Default")
      (node (ref "JP2") (pin "1") (pinfunction "1_1") (pintype "passive"))
      (node (ref "U$1") (pin "31") (pinfunction "31_31") (pintype "bidirectional"))
    )
    (net (code "9") (name "33") (class "Default")
      (node (ref "JP29") (pin "1") (pinfunction "1_1") (pintype "passive"))
      (node (ref "U$1") (pin "33") (pinfunction "33_33") (pintype "bidirectional"))
    )
    (net (code "10") (name "35") (class "Default")
      (node (ref "JP28") (pin "1") (pinfunction "1_1") (pintype "passive"))
      (node (ref "U$1") (pin "35") (pinfunction "35_35") (pintype "bidirectional"))
    )
    (net (code "11") (name "37") (class "Default")
      (node (ref "JP22") (pin "1") (pinfunction "1_1") (pintype "passive"))
      (node (ref "U$1") (pin "37") (pinfunction "37_37") (pintype "bidirectional"))
    )
    (net (code "12") (name "BED") (class "Default")
      (node (ref "R47") (pin "2") (pinfunction "2_2") (pintype "passive"))
      (node (ref "R49") (pin "2") (pinfunction "2_2") (pintype "passive"))
      (node (ref "U$1") (pin "7") (pinfunction "7_7") (pintype "bidirectional"))
    )
    (net (code "13") (name "BEEPER") (class "Default")
      (node (ref "SV4") (pin "2") (pinfunction "2_2") (pintype "passive"))
      (node (ref "U$1") (pin "41") (pinfunction "41_41") (pintype "bidirectional"))
    )
    (net (code "14") (name "CANRX") (class "Default")
      (node (ref "JP52") (pin "1") (pinfunction "1_1") (pintype "passive"))
      (node (ref "U$1") (pin "CANRX") (pinfunction "CANRX_CANRX") (pintype "bidirectional"))
    )
    (net (code "15") (name "CANTX") (class "Default")
      (node (ref "JP26") (pin "1") (pinfunction "1_1") (pintype "passive"))
      (node (ref "U$1") (pin "CANTX") (pinfunction "CANTX_CANTX") (pintype "bidirectional"))
    )
    (net (code "16") (name "CARDDETECT") (class "Default")
      (node (ref "SV5") (pin "8") (pinfunction "8_8") (pintype "passive"))
      (node (ref "U$1") (pin "TX3") (pinfunction "TX3_TX3") (pintype "bidirectional"))
    )
    (net (code "17") (name "CS0") (class "Default")
      (node (ref "JP21") (pin "1") (pinfunction "1_1") (pintype "passive"))
      (node (ref "U$1") (pin "10") (pinfunction "10_10") (pintype "bidirectional"))
    )
    (net (code "18") (name "CS1") (class "Default")
      (node (ref "SV5") (pin "3") (pinfunction "3_3") (pintype "passive"))
      (node (ref "U$1") (pin "4") (pinfunction "4_4") (pintype "bidirectional"))
    )
    (net (code "19") (name "DAC0") (class "Default")
      (node (ref "JP53") (pin "1") (pinfunction "1_1") (pintype "passive"))
      (node (ref "U$1") (pin "DAC0") (pinfunction "DAC0_DAC0") (pintype "bidirectional"))
    )
    (net (code "20") (name "DAC1") (class "Default")
      (node (ref "JP54") (pin "1") (pinfunction "1_1") (pintype "passive"))
      (node (ref "U$1") (pin "DAC1") (pinfunction "DAC1_DAC1") (pintype "bidirectional"))
    )
    (net (code "21") (name "E-DIR") (class "Default")
      (node (ref "STEPSTICK-Z2") (pin "DIR") (pinfunction "DIR_DIR") (pintype "bidirectional"))
      (node (ref "U$1") (pin "A6") (pinfunction "A6_A6") (pintype "bidirectional"))
    )
    (net (code "22") (name "E-ENA") (class "Default")
      (node (ref "R7") (pin "2") (pinfunction "2_2") (pintype "passive"))
      (node (ref "STEPSTICK-Z2") (pin "ENABLE") (pinfunction "EN_ENABLE") (pintype "bidirectional"))
      (node (ref "U$1") (pin "A8") (pinfunction "A8_A8") (pintype "bidirectional"))
    )
    (net (code "23") (name "E-STP") (class "Default")
      (node (ref "STEPSTICK-Z2") (pin "STP") (pinfunction "STEP_STP") (pintype "bidirectional"))
      (node (ref "U$1") (pin "A7") (pinfunction "A7_A7") (pintype "bidirectional"))
    )
    (net (code "24") (name "ENCA") (class "Default")
      (node (ref "SV5") (pin "4") (pinfunction "4_4") (pintype "passive"))
      (node (ref "U$1") (pin "52") (pinfunction "52_52") (pintype "bidirectional"))
    )
    (net (code "25") (name "ENCB") (class "Default")
      (node (ref "SV5") (pin "6") (pinfunction "6_6") (pintype "passive"))
      (node (ref "U$1") (pin "50") (pinfunction "50_50") (pintype "bidirectional"))
    )
    (net (code "26") (name "ENCP") (class "Default")
      (node (ref "SV4") (pin "1") (pinfunction "1_1") (pintype "passive"))
      (node (ref "U$1") (pin "48") (pinfunction "48_48") (pintype "bidirectional"))
    )
    (net (code "27") (name "FAN0") (class "Default")
      (node (ref "U$1") (pin "8") (pinfunction "8_8") (pintype "bidirectional"))
      (node (ref "X1") (pin "1") (pinfunction "S_1") (pintype "passive"))
    )
    (net (code "28") (name "FAN1") (class "Default")
      (node (ref "R35") (pin "2") (pinfunction "2_2") (pintype "passive"))
      (node (ref "U$1") (pin "11") (pinfunction "11_11") (pintype "bidirectional"))
    )
    (net (code "29") (name "FAN2") (class "Default")
      (node (ref "R27") (pin "2") (pinfunction "2_2") (pintype "passive"))
      (node (ref "U$1") (pin "12") (pinfunction "12_12") (pintype "bidirectional"))
    )
    (net (code "30") (name "FAN3") (class "Default")
      (node (ref "R40") (pin "2") (pinfunction "2_2") (pintype "passive"))
      (node (ref "U$1") (pin "9") (pinfunction "9_9") (pintype "bidirectional"))
    )
    (net (code "31") (name "GND") (class "Default")
      (node (ref "C1") (pin "2") (pinfunction "2_2") (pintype "passive"))
      (node (ref "C10") (pin "-") (pinfunction "-_-") (pintype "passive"))
      (node (ref "C11") (pin "2") (pinfunction "2_2") (pintype "passive"))
      (node (ref "C12") (pin "2") (pinfunction "2_2") (pintype "passive"))
      (node (ref "C14") (pin "2") (pinfunction "2_2") (pintype "passive"))
      (node (ref "C16") (pin "2") (pinfunction "2_2") (pintype "passive"))
      (node (ref "C17") (pin "2") (pinfunction "2_2") (pintype "passive"))
      (node (ref "C19") (pin "2") (pinfunction "2_2") (pintype "passive"))
      (node (ref "C2") (pin "2") (pinfunction "2_2") (pintype "passive"))
      (node (ref "C21") (pin "2") (pinfunction "2_2") (pintype "passive"))
      (node (ref "C3") (pin "-") (pinfunction "-_-") (pintype "passive"))
      (node (ref "C32") (pin "1") (pinfunction "1_1") (pintype "passive"))
      (node (ref "C4") (pin "2") (pinfunction "2_2") (pintype "passive"))
      (node (ref "C46") (pin "1") (pinfunction "1_1") (pintype "passive"))
      (node (ref "C47") (pin "1") (pinfunction "1_1") (pintype "passive"))
      (node (ref "C49") (pin "1") (pinfunction "1_1") (pintype "passive"))
      (node (ref "C5") (pin "2") (pinfunction "2_2") (pintype "passive"))
      (node (ref "C51") (pin "1") (pinfunction "1_1") (pintype "passive"))
      (node (ref "C57") (pin "2") (pinfunction "2_2") (pintype "passive"))
      (node (ref "C59") (pin "2") (pinfunction "2_2") (pintype "passive"))
      (node (ref "C6") (pin "-") (pinfunction "-_-") (pintype "passive"))
      (node (ref "C61") (pin "2") (pinfunction "2_2") (pintype "passive"))
      (node (ref "C63") (pin "2") (pinfunction "2_2") (pintype "passive"))
      (node (ref "C65") (pin "-") (pinfunction "-_-") (pintype "passive"))
      (node (ref "C67") (pin "-") (pinfunction "-_-") (pintype "passive"))
      (node (ref "C7") (pin "2") (pinfunction "2_2") (pintype "passive"))
      (node (ref "C8") (pin "-") (pinfunction "-_-") (pintype "passive"))
      (node (ref "C9") (pin "2") (pinfunction "2_2") (pintype "passive"))
      (node (ref "D4") (pin "A") (pinfunction "A_A") (pintype "passive"))
      (node (ref "FET1") (pin "S") (pinfunction "S_S") (pintype "bidirectional"))
      (node (ref "FET2") (pin "S") (pinfunction "S_S") (pintype "bidirectional"))
      (node (ref "H16") (pin "2") (pinfunction "2_2") (pintype "passive"))
      (node (ref "H17") (pin "2") (pinfunction "2_2") (pintype "passive"))
      (node (ref "H18") (pin "2") (pinfunction "2_2") (pintype "passive"))
      (node (ref "H19") (pin "2") (pinfunction "2_2") (pintype "passive"))
      (node (ref "H21") (pin "1") (pinfunction "1_1") (pintype "passive"))
      (node (ref "IC2") (pin "1") (pinfunction "A0_1") (pintype "input"))
      (node (ref "IC2") (pin "2") (pinfunction "A1_2") (pintype "input"))
      (node (ref "IC2") (pin "3") (pinfunction "A2_3") (pintype "input"))
      (node (ref "IC2") (pin "4") (pinfunction "GND_4") (pintype "power_in"))
      (node (ref "IC2") (pin "7") (pinfunction "WP_7") (pintype "input"))
      (node (ref "IC5") (pin "3") (pinfunction "GND_3") (pintype "power_in"))
      (node (ref "IC5") (pin "5") (pinfunction "~{ON}/OFF_5") (pintype "input"))
      (node (ref "JP10") (pin "1") (pinfunction "1_1") (pintype "passive"))
      (node (ref "JP12") (pin "1") (pinfunction "1_1") (pintype "passive"))
      (node (ref "JP33") (pin "1") (pinfunction "1_1") (pintype "passive"))
      (node (ref "JP34") (pin "1") (pinfunction "1_1") (pintype "passive"))
      (node (ref "JP35") (pin "1") (pinfunction "1_1") (pintype "passive"))
      (node (ref "JP36") (pin "1") (pinfunction "1_1") (pintype "passive"))
      (node (ref "JP37") (pin "1") (pinfunction "1_1") (pintype "passive"))
      (node (ref "JP38") (pin "1") (pinfunction "1_1") (pintype "passive"))
      (node (ref "JP39") (pin "1") (pinfunction "1_1") (pintype "passive"))
      (node (ref "JP40") (pin "1") (pinfunction "1_1") (pintype "passive"))
      (node (ref "JP41") (pin "1") (pinfunction "1_1") (pintype "passive"))
      (node (ref "JP42") (pin "1") (pinfunction "1_1") (pintype "passive"))
      (node (ref "JP43") (pin "1") (pinfunction "1_1") (pintype "passive"))
      (node (ref "JP44") (pin "1") (pinfunction "1_1") (pintype "passive"))
      (node (ref "JP45") (pin "1") (pinfunction "1_1") (pintype "passive"))
      (node (ref "JP8") (pin "1") (pinfunction "1_1") (pintype "passive"))
      (node (ref "LED5") (pin "C") (pinfunction "C_C") (pintype "passive"))
      (node (ref "LED6") (pin "C") (pinfunction "C_C") (pintype "passive"))
      (node (ref "LED7") (pin "C") (pinfunction "C_C") (pintype "passive"))
      (node (ref "P2") (pin "2") (pinfunction "2_2") (pintype "passive"))
      (node (ref "P5") (pin "2") (pinfunction "2_2") (pintype "passive"))
      (node (ref "P7") (pin "2") (pinfunction "2_2") (pintype "passive"))
      (node (ref "Q1") (pin "2") (pinfunction "S_2") (pintype "passive"))
      (node (ref "Q2") (pin "2") (pinfunction "S_2") (pintype "passive"))
      (node (ref "Q3") (pin "2") (pinfunction "S_2") (pintype "passive"))
      (node (ref "R2") (pin "1") (pinfunction "1_1") (pintype "passive"))
      (node (ref "R22") (pin "1") (pinfunction "1_1") (pintype "passive"))
      (node (ref "R36") (pin "2") (pinfunction "2_2") (pintype "passive"))
      (node (ref "R37") (pin "2") (pinfunction "2_2") (pintype "passive"))
      (node (ref "R4") (pin "1") (pinfunction "1_1") (pintype "passive"))
      (node (ref "R41") (pin "2") (pinfunction "2_2") (pintype "passive"))
      (node (ref "R48") (pin "2") (pinfunction "2_2") (pintype "passive"))
      (node (ref "R51") (pin "2") (pinfunction "2_2") (pintype "passive"))
      (node (ref "R6") (pin "1") (pinfunction "1_1") (pintype "passive"))
      (node (ref "R8") (pin "1") (pinfunction "1_1") (pintype "passive"))
      (node (ref "RESET") (pin "2") (pinfunction "2_2") (pintype "bidirectional"))
      (node (ref "STEPSTICK-X") (pin "GND") (pinfunction "GNDM_GND") (pintype "bidirectional"))
      (node (ref "STEPSTICK-X") (pin "GND1") (pinfunction "GND_GND1") (pintype "bidirectional"))
      (node (ref "STEPSTICK-Y") (pin "GND") (pinfunction "GNDM_GND") (pintype "bidirectional"))
      (node (ref "STEPSTICK-Y") (pin "GND1") (pinfunction "GND_GND1") (pintype "bidirectional"))
      (node (ref "STEPSTICK-Z1") (pin "GND") (pinfunction "GNDM_GND") (pintype "bidirectional"))
      (node (ref "STEPSTICK-Z1") (pin "GND1") (pinfunction "GND_GND1") (pintype "bidirectional"))
      (node (ref "STEPSTICK-Z2") (pin "GND") (pinfunction "GNDM_GND") (pintype "bidirectional"))
      (node (ref "STEPSTICK-Z2") (pin "GND1") (pinfunction "GND_GND1") (pintype "bidirectional"))
      (node (ref "SV4") (pin "10") (pinfunction "10_10") (pintype "passive"))
      (node (ref "SV5") (pin "10") (pinfunction "10_10") (pintype "passive"))
      (node (ref "THERMISTOR") (pin "2") (pinfunction "2_2") (pintype "passive"))
      (node (ref "U$1") (pin "5V_ICSP") (pinfunction "5V_ICSP_5V_ICSP") (pintype "bidirectional"))
      (node (ref "U$1") (pin "GND_1") (pinfunction "GND_1_GND_1") (pintype "bidirectional"))
      (node (ref "U$1") (pin "GND_2") (pinfunction "GND_2_GND_2") (pintype "bidirectional"))
      (node (ref "U$1") (pin "GND_A") (pinfunction "GND_A_GND_A") (pintype "bidirectional"))
      (node (ref "U$1") (pin "GND_B") (pinfunction "GND_B_GND_B") (pintype "bidirectional"))
      (node (ref "X1") (pin "4") (pinfunction "S_4") (pintype "passive"))
    )
    (net (code "32") (name "HOT1") (class "Default")
      (node (ref "R50") (pin "2") (pinfunction "2_2") (pintype "passive"))
      (node (ref "R52") (pin "1") (pinfunction "1_1") (pintype "passive"))
      (node (ref "U$1") (pin "13") (pinfunction "13_13") (pintype "bidirectional"))
    )
    (net (code "33") (name "LCD4") (class "Default")
      (node (ref "SV4") (pin "6") (pinfunction "6_6") (pintype "passive"))
      (node (ref "U$1") (pin "44") (pinfunction "44_44") (pintype "bidirectional"))
    )
    (net (code "34") (name "LCD5") (class "Default")
      (node (ref "SV4") (pin "5") (pinfunction "5_5") (pintype "passive"))
      (node (ref "U$1") (pin "45") (pinfunction "45_45") (pintype "bidirectional"))
    )
    (net (code "35") (name "LCD6") (class "Default")
      (node (ref "SV4") (pin "8") (pinfunction "8_8") (pintype "passive"))
      (node (ref "U$1") (pin "46") (pinfunction "46_46") (pintype "bidirectional"))
    )
    (net (code "36") (name "LCD7") (class "Default")
      (node (ref "SV4") (pin "7") (pinfunction "7_7") (pintype "passive"))
      (node (ref "U$1") (pin "47") (pinfunction "47_47") (pintype "bidirectional"))
    )
    (net (code "37") (name "LCD_ENA") (class "Default")
      (node (ref "SV4") (pin "4") (pinfunction "4_4") (pintype "passive"))
      (node (ref "U$1") (pin "43") (pinfunction "43_43") (pintype "bidirectional"))
    )
    (net (code "38") (name "LCD_RS") (class "Default")
      (node (ref "SV4") (pin "3") (pinfunction "3_3") (pintype "passive"))
      (node (ref "U$1") (pin "42") (pinfunction "42_42") (pintype "bidirectional"))
    )
    (net (code "39") (name "MISO") (class "Default")
      (node (ref "SV5") (pin "2") (pinfunction "2_2") (pintype "passive"))
      (node (ref "U$1") (pin "MISO_ICSP") (pinfunction "MISO_ICSP_MISO_ICSP") (pintype "bidirectional"))
    )
    (net (code "40") (name "MOSI") (class "Default")
      (node (ref "SV5") (pin "5") (pinfunction "5_5") (pintype "passive"))
      (node (ref "U$1") (pin "MOSI_ICSP") (pinfunction "MOSI_ICSP_MOSI_ICSP") (pintype "bidirectional"))
    )
    (net (code "41") (name "NTC1") (class "Default")
      (node (ref "R24") (pin "2") (pinfunction "2_2") (pintype "passive"))
      (node (ref "U$1") (pin "A0") (pinfunction "A0_A0") (pintype "bidirectional"))
    )
    (net (code "42") (name "NTC2") (class "Default")
      (node (ref "R32") (pin "2") (pinfunction "2_2") (pintype "passive"))
      (node (ref "U$1") (pin "A1") (pinfunction "A1_A1") (pintype "bidirectional"))
    )
    (net (code "43") (name "NTC3") (class "Default")
      (node (ref "R33") (pin "2") (pinfunction "2_2") (pintype "passive"))
      (node (ref "U$1") (pin "A2") (pinfunction "A2_A2") (pintype "bidirectional"))
    )
    (net (code "44") (name "NTC4") (class "Default")
      (node (ref "R34") (pin "2") (pinfunction "2_2") (pintype "passive"))
      (node (ref "U$1") (pin "A5") (pinfunction "A5_A5") (pintype "bidirectional"))
    )
    (net (code "45") (name "Net-(C3-Pad+)") (class "Default")
      (node (ref "C3") (pin "+") (pinfunction "+_+") (pintype "passive"))
      (node (ref "C4") (pin "1") (pinfunction "1_1") (pintype "passive"))
      (node (ref "L2") (pin "1") (pinfunction "1_1") (pintype "passive"))
      (node (ref "STEPSTICK-X") (pin "VMOT") (pinfunction "VMOT_VMOT") (pintype "bidirectional"))
    )
    (net (code "46") (name "Net-(C6-Pad+)") (class "Default")
      (node (ref "C6") (pin "+") (pinfunction "+_+") (pintype "passive"))
      (node (ref "C9") (pin "1") (pinfunction "1_1") (pintype "passive"))
      (node (ref "L4") (pin "1") (pinfunction "1_1") (pintype "passive"))
      (node (ref "STEPSTICK-Y") (pin "VMOT") (pinfunction "VMOT_VMOT") (pintype "bidirectional"))
    )
    (net (code "47") (name "Net-(C10-Pad+)") (class "Default")
      (node (ref "C10") (pin "+") (pinfunction "+_+") (pintype "passive"))
      (node (ref "C19") (pin "1") (pinfunction "1_1") (pintype "passive"))
      (node (ref "L8") (pin "1") (pinfunction "1_1") (pintype "passive"))
      (node (ref "STEPSTICK-Z2") (pin "VMOT") (pinfunction "VMOT_VMOT") (pintype "bidirectional"))
    )
    (net (code "48") (name "Net-(C14-Pad1)") (class "Default")
      (node (ref "C14") (pin "1") (pinfunction "1_1") (pintype "passive"))
      (node (ref "C8") (pin "+") (pinfunction "+_+") (pintype "passive"))
      (node (ref "L6") (pin "1") (pinfunction "1_1") (pintype "passive"))
      (node (ref "STEPSTICK-Z1") (pin "VMOT") (pinfunction "VMOT_VMOT") (pintype "bidirectional"))
    )
    (net (code "49") (name "Net-(C57-Pad1)") (class "Default")
      (node (ref "C57") (pin "1") (pinfunction "1_1") (pintype "passive"))
      (node (ref "H17") (pin "1") (pinfunction "1_1") (pintype "passive"))
      (node (ref "R24") (pin "1") (pinfunction "1_1") (pintype "passive"))
      (node (ref "R28") (pin "1") (pinfunction "1_1") (pintype "passive"))
    )
    (net (code "50") (name "Net-(C59-Pad1)") (class "Default")
      (node (ref "C59") (pin "1") (pinfunction "1_1") (pintype "passive"))
      (node (ref "H18") (pin "1") (pinfunction "1_1") (pintype "passive"))
      (node (ref "R29") (pin "1") (pinfunction "1_1") (pintype "passive"))
      (node (ref "R32") (pin "1") (pinfunction "1_1") (pintype "passive"))
    )
    (net (code "51") (name "Net-(C61-Pad1)") (class "Default")
      (node (ref "C61") (pin "1") (pinfunction "1_1") (pintype "passive"))
      (node (ref "H19") (pin "1") (pinfunction "1_1") (pintype "passive"))
      (node (ref "R30") (pin "1") (pinfunction "1_1") (pintype "passive"))
      (node (ref "R33") (pin "1") (pinfunction "1_1") (pintype "passive"))
    )
    (net (code "52") (name "Net-(C63-Pad1)") (class "Default")
      (node (ref "C63") (pin "1") (pinfunction "1_1") (pintype "passive"))
      (node (ref "R31") (pin "1") (pinfunction "1_1") (pintype "passive"))
      (node (ref "R34") (pin "1") (pinfunction "1_1") (pintype "passive"))
      (node (ref "THERMISTOR") (pin "1") (pinfunction "1_1") (pintype "passive"))
    )
    (net (code "53") (name "Net-(C67-Pad+)") (class "Default")
      (node (ref "C67") (pin "+") (pinfunction "+_+") (pintype "passive"))
      (node (ref "C68") (pin "2") (pinfunction "2_2") (pintype "passive"))
      (node (ref "L17") (pin "1") (pinfunction "1_1") (pintype "passive"))
      (node (ref "L19") (pin "2") (pinfunction "2_2") (pintype "passive"))
      (node (ref "R23") (pin "2") (pinfunction "2_2") (pintype "passive"))
    )
    (net (code "54") (name "Net-(D3-PadA)") (class "Default")
      (node (ref "D3") (pin "A") (pinfunction "A_A") (pintype "passive"))
      (node (ref "L15") (pin "2") (pinfunction "2_2") (pintype "passive"))
    )
    (net (code "55") (name "Net-(FET1-PadD)") (class "Default")
      (node (ref "FET1") (pin "D") (pinfunction "D_D") (pintype "bidirectional"))
      (node (ref "P4") (pin "2") (pinfunction "2_2") (pintype "passive"))
    )
    (net (code "56") (name "Net-(FET1-PadG)") (class "Default")
      (node (ref "FET1") (pin "G") (pinfunction "G_G") (pintype "bidirectional"))
      (node (ref "R50") (pin "1") (pinfunction "1_1") (pintype "passive"))
      (node (ref "R51") (pin "1") (pinfunction "1_1") (pintype "passive"))
    )
    (net (code "57") (name "Net-(FET2-PadD)") (class "Default")
      (node (ref "FET2") (pin "D") (pinfunction "D_D") (pintype "bidirectional"))
      (node (ref "P3") (pin "2") (pinfunction "2_2") (pintype "passive"))
    )
    (net (code "58") (name "Net-(FET2-PadG)") (class "Default")
      (node (ref "FET2") (pin "G") (pinfunction "G_G") (pintype "bidirectional"))
      (node (ref "R47") (pin "1") (pinfunction "1_1") (pintype "passive"))
      (node (ref "R48") (pin "1") (pinfunction "1_1") (pintype "passive"))
    )
    (net (code "59") (name "Net-(IC5-FB)") (class "Default")
      (node (ref "C68") (pin "1") (pinfunction "1_1") (pintype "passive"))
      (node (ref "IC5") (pin "4") (pinfunction "FB_4") (pintype "input"))
      (node (ref "R22") (pin "2") (pinfunction "2_2") (pintype "passive"))
      (node (ref "R23") (pin "1") (pinfunction "1_1") (pintype "passive"))
    )
    (net (code "60") (name "Net-(IC5-OUT)") (class "Default")
      (node (ref "D4") (pin "C") (pinfunction "C_C") (pintype "passive"))
      (node (ref "IC5") (pin "2") (pinfunction "OUT_2") (pintype "output"))
      (node (ref "L19") (pin "1") (pinfunction "1_1") (pintype "passive"))
    )
    (net (code "61") (name "Net-(IC5-VIN)") (class "Default")
      (node (ref "C65") (pin "+") (pinfunction "+_+") (pintype "passive"))
      (node (ref "D3") (pin "C") (pinfunction "C_C") (pintype "passive"))
      (node (ref "IC5") (pin "1") (pinfunction "VIN_1") (pintype "input"))
      (node (ref "JP7") (pin "3") (pinfunction "3_3") (pintype "passive"))
    )
    (net (code "62") (name "Net-(J1-Pad1)") (class "Default")
      (node (ref "J1") (pin "1") (pinfunction "1_1") (pintype "passive"))
      (node (ref "STEPSTICK-X") (pin "1A") (pinfunction "1A_1A") (pintype "bidirectional"))
    )
    (net (code "63") (name "Net-(J1-Pad2)") (class "Default")
      (node (ref "J1") (pin "2") (pinfunction "2_2") (pintype "passive"))
      (node (ref "STEPSTICK-X") (pin "1B") (pinfunction "1B_1B") (pintype "bidirectional"))
    )
    (net (code "64") (name "Net-(J1-Pad3)") (class "Default")
      (node (ref "J1") (pin "3") (pinfunction "3_3") (pintype "passive"))
      (node (ref "STEPSTICK-X") (pin "2A") (pinfunction "2A_2A") (pintype "bidirectional"))
    )
    (net (code "65") (name "Net-(J1-Pad4)") (class "Default")
      (node (ref "J1") (pin "4") (pinfunction "4_4") (pintype "passive"))
      (node (ref "STEPSTICK-X") (pin "2B") (pinfunction "2B_2B") (pintype "bidirectional"))
    )
    (net (code "66") (name "Net-(J2-Pad1)") (class "Default")
      (node (ref "J2") (pin "1") (pinfunction "1_1") (pintype "passive"))
      (node (ref "STEPSTICK-Y") (pin "1A") (pinfunction "1A_1A") (pintype "bidirectional"))
    )
    (net (code "67") (name "Net-(J2-Pad2)") (class "Default")
      (node (ref "J2") (pin "2") (pinfunction "2_2") (pintype "passive"))
      (node (ref "STEPSTICK-Y") (pin "1B") (pinfunction "1B_1B") (pintype "bidirectional"))
    )
    (net (code "68") (name "Net-(J2-Pad3)") (class "Default")
      (node (ref "J2") (pin "3") (pinfunction "3_3") (pintype "passive"))
      (node (ref "STEPSTICK-Y") (pin "2A") (pinfunction "2A_2A") (pintype "bidirectional"))
    )
    (net (code "69") (name "Net-(J2-Pad4)") (class "Default")
      (node (ref "J2") (pin "4") (pinfunction "4_4") (pintype "passive"))
      (node (ref "STEPSTICK-Y") (pin "2B") (pinfunction "2B_2B") (pintype "bidirectional"))
    )
    (net (code "70") (name "Net-(J3-Pad1)") (class "Default")
      (node (ref "J3") (pin "1") (pinfunction "1_1") (pintype "passive"))
      (node (ref "STEPSTICK-Z1") (pin "1A") (pinfunction "1A_1A") (pintype "bidirectional"))
    )
    (net (code "71") (name "Net-(J3-Pad2)") (class "Default")
      (node (ref "J3") (pin "2") (pinfunction "2_2") (pintype "passive"))
      (node (ref "STEPSTICK-Z1") (pin "1B") (pinfunction "1B_1B") (pintype "bidirectional"))
    )
    (net (code "72") (name "Net-(J3-Pad3)") (class "Default")
      (node (ref "J3") (pin "3") (pinfunction "3_3") (pintype "passive"))
      (node (ref "STEPSTICK-Z1") (pin "2A") (pinfunction "2A_2A") (pintype "bidirectional"))
    )
    (net (code "73") (name "Net-(J3-Pad4)") (class "Default")
      (node (ref "J3") (pin "4") (pinfunction "4_4") (pintype "passive"))
      (node (ref "STEPSTICK-Z1") (pin "2B") (pinfunction "2B_2B") (pintype "bidirectional"))
    )
    (net (code "74") (name "Net-(J4-Pad1)") (class "Default")
      (node (ref "J4") (pin "1") (pinfunction "1_1") (pintype "passive"))
      (node (ref "STEPSTICK-Z2") (pin "1A") (pinfunction "1A_1A") (pintype "bidirectional"))
    )
    (net (code "75") (name "Net-(J4-Pad2)") (class "Default")
      (node (ref "J4") (pin "2") (pinfunction "2_2") (pintype "passive"))
      (node (ref "STEPSTICK-Z2") (pin "1B") (pinfunction "1B_1B") (pintype "bidirectional"))
    )
    (net (code "76") (name "Net-(J4-Pad3)") (class "Default")
      (node (ref "J4") (pin "3") (pinfunction "3_3") (pintype "passive"))
      (node (ref "STEPSTICK-Z2") (pin "2A") (pinfunction "2A_2A") (pintype "bidirectional"))
    )
    (net (code "77") (name "Net-(J4-Pad4)") (class "Default")
      (node (ref "J4") (pin "4") (pinfunction "4_4") (pintype "passive"))
      (node (ref "STEPSTICK-Z2") (pin "2B") (pinfunction "2B_2B") (pintype "bidirectional"))
    )
    (net (code "78") (name "Net-(JP8-Pad3)") (class "Default")
      (node (ref "JP8") (pin "3") (pinfunction "3_3") (pintype "passive"))
      (node (ref "R16") (pin "2") (pinfunction "2_2") (pintype "passive"))
    )
    (net (code "79") (name "Net-(JP9-Pad2)") (class "Default")
      (node (ref "JP9") (pin "2") (pinfunction "2_2") (pintype "passive"))
      (node (ref "R8") (pin "2") (pinfunction "2_2") (pintype "passive"))
      (node (ref "STEPSTICK-Z2") (pin "MS1") (pinfunction "MS1_MS1") (pintype "bidirectional"))
    )
    (net (code "80") (name "Net-(JP10-Pad3)") (class "Default")
      (node (ref "JP10") (pin "3") (pinfunction "3_3") (pintype "passive"))
      (node (ref "R18") (pin "2") (pinfunction "2_2") (pintype "passive"))
    )
    (net (code "81") (name "Net-(JP11-Pad2)") (class "Default")
      (node (ref "JP11") (pin "2") (pinfunction "2_2") (pintype "passive"))
      (node (ref "STEPSTICK-Z2") (pin "MS2") (pinfunction "MS2_MS2") (pintype "bidirectional"))
    )
    (net (code "82") (name "Net-(JP12-Pad3)") (class "Default")
      (node (ref "JP12") (pin "3") (pinfunction "3_3") (pintype "passive"))
      (node (ref "R20") (pin "2") (pinfunction "2_2") (pintype "passive"))
    )
    (net (code "83") (name "Net-(JP13-Pad2)") (class "Default")
      (node (ref "JP13") (pin "2") (pinfunction "2_2") (pintype "passive"))
      (node (ref "STEPSTICK-Z2") (pin "MS3") (pinfunction "MS3_MS3") (pintype "bidirectional"))
    )
    (net (code "84") (name "Net-(JP46-Pad2)") (class "Default")
      (node (ref "JP46") (pin "2") (pinfunction "2_2") (pintype "passive"))
      (node (ref "R6") (pin "2") (pinfunction "2_2") (pintype "passive"))
      (node (ref "STEPSTICK-Z1") (pin "MS1") (pinfunction "MS1_MS1") (pintype "bidirectional"))
    )
    (net (code "85") (name "Net-(JP47-Pad2)") (class "Default")
      (node (ref "JP47") (pin "2") (pinfunction "2_2") (pintype "passive"))
      (node (ref "STEPSTICK-Z1") (pin "MS2") (pinfunction "MS2_MS2") (pintype "bidirectional"))
    )
    (net (code "86") (name "Net-(JP48-Pad2)") (class "Default")
      (node (ref "JP48") (pin "2") (pinfunction "2_2") (pintype "passive"))
      (node (ref "STEPSTICK-Z1") (pin "MS3") (pinfunction "MS3_MS3") (pintype "bidirectional"))
    )
    (net (code "87") (name "Net-(JP49-Pad2)") (class "Default")
      (node (ref "JP49") (pin "2") (pinfunction "2_2") (pintype "passive"))
      (node (ref "R4") (pin "2") (pinfunction "2_2") (pintype "passive"))
      (node (ref "STEPSTICK-Y") (pin "MS1") (pinfunction "MS1_MS1") (pintype "bidirectional"))
    )
    (net (code "88") (name "Net-(JP50-Pad2)") (class "Default")
      (node (ref "JP50") (pin "2") (pinfunction "2_2") (pintype "passive"))
      (node (ref "STEPSTICK-Y") (pin "MS2") (pinfunction "MS2_MS2") (pintype "bidirectional"))
    )
    (net (code "89") (name "Net-(JP51-Pad2)") (class "Default")
      (node (ref "JP51") (pin "2") (pinfunction "2_2") (pintype "passive"))
      (node (ref "STEPSTICK-Y") (pin "MS3") (pinfunction "MS3_MS3") (pintype "bidirectional"))
    )
    (net (code "90") (name "Net-(JP55-Pad2)") (class "Default")
      (node (ref "JP55") (pin "2") (pinfunction "2_2") (pintype "passive"))
      (node (ref "R2") (pin "2") (pinfunction "2_2") (pintype "passive"))
      (node (ref "STEPSTICK-X") (pin "MS1") (pinfunction "MS1_MS1") (pintype "bidirectional"))
    )
    (net (code "91") (name "Net-(JP56-Pad2)") (class "Default")
      (node (ref "JP56") (pin "2") (pinfunction "2_2") (pintype "passive"))
      (node (ref "STEPSTICK-X") (pin "MS2") (pinfunction "MS2_MS2") (pintype "bidirectional"))
    )
    (net (code "92") (name "Net-(JP57-Pad2)") (class "Default")
      (node (ref "JP57") (pin "2") (pinfunction "2_2") (pintype "passive"))
      (node (ref "STEPSTICK-X") (pin "MS3") (pinfunction "MS3_MS3") (pintype "bidirectional"))
    )
    (net (code "93") (name "Net-(JP62-Pad1)") (class "Default")
      (node (ref "JP62") (pin "1") (pinfunction "1_1") (pintype "passive"))
      (node (ref "U$1") (pin "28") (pinfunction "28_28") (pintype "bidirectional"))
    )
    (net (code "94") (name "Net-(JP63-Pad1)") (class "Default")
      (node (ref "JP63") (pin "1") (pinfunction "1_1") (pintype "passive"))
      (node (ref "U$1") (pin "32") (pinfunction "32_32") (pintype "bidirectional"))
    )
    (net (code "95") (name "Net-(JP64-Pad1)") (class "Default")
      (node (ref "JP64") (pin "1") (pinfunction "1_1") (pintype "passive"))
      (node (ref "U$1") (pin "36") (pinfunction "36_36") (pintype "bidirectional"))
    )
    (net (code "96") (name "Net-(JP65-Pad1)") (class "Default")
      (node (ref "JP65") (pin "1") (pinfunction "1_1") (pintype "passive"))
      (node (ref "U$1") (pin "39") (pinfunction "39_39") (pintype "bidirectional"))
    )
    (net (code "97") (name "Net-(JP66-Pad1)") (class "Default")
      (node (ref "JP66") (pin "1") (pinfunction "1_1") (pintype "passive"))
      (node (ref "U$1") (pin "49") (pinfunction "49_49") (pintype "bidirectional"))
    )
    (net (code "98") (name "Net-(JP67-Pad1)") (class "Default")
      (node (ref "JP67") (pin "1") (pinfunction "1_1") (pintype "passive"))
      (node (ref "U$1") (pin "51") (pinfunction "51_51") (pintype "bidirectional"))
    )
    (net (code "99") (name "Net-(JP68-Pad1)") (class "Default")
      (node (ref "JP68") (pin "1") (pinfunction "1_1") (pintype "passive"))
      (node (ref "U$1") (pin "53") (pinfunction "53_53") (pintype "bidirectional"))
    )
    (net (code "100") (name "Net-(JP69-Pad1)") (class "Default")
      (node (ref "JP69") (pin "1") (pinfunction "1_1") (pintype "passive"))
      (node (ref "U$1") (pin "A3") (pinfunction "A3_A3") (pintype "bidirectional"))
    )
    (net (code "101") (name "Net-(JP70-Pad1)") (class "Default")
      (node (ref "JP70") (pin "1") (pinfunction "1_1") (pintype "passive"))
      (node (ref "U$1") (pin "A4") (pinfunction "A4_A4") (pintype "bidirectional"))
    )
    (net (code "102") (name "Net-(JP71-Pad1)") (class "Default")
      (node (ref "JP71") (pin "1") (pinfunction "1_1") (pintype "passive"))
      (node (ref "U$1") (pin "A11") (pinfunction "A11_A11") (pintype "bidirectional"))
    )
    (net (code "103") (name "Net-(JP72-Pad1)") (class "Default")
      (node (ref "JP72") (pin "1") (pinfunction "1_1") (pintype "passive"))
      (node (ref "U$1") (pin "23") (pinfunction "23_23") (pintype "bidirectional"))
    )
    (net (code "104") (name "Net-(JP73-Pad1)") (class "Default")
      (node (ref "JP73") (pin "1") (pinfunction "1_1") (pintype "passive"))
      (node (ref "U$1") (pin "24") (pinfunction "24_24") (pintype "bidirectional"))
    )
    (net (code "105") (name "Net-(LED1-PadA)") (class "Default")
      (node (ref "LED1") (pin "A") (pinfunction "A_A") (pintype "passive"))
      (node (ref "R26") (pin "2") (pinfunction "2_2") (pintype "passive"))
    )
    (net (code "106") (name "Net-(LED2-PadA)") (class "Default")
      (node (ref "LED2") (pin "A") (pinfunction "A_A") (pintype "passive"))
      (node (ref "R38") (pin "2") (pinfunction "2_2") (pintype "passive"))
    )
    (net (code "107") (name "Net-(LED3-PadA)") (class "Default")
      (node (ref "LED3") (pin "A") (pinfunction "A_A") (pintype "passive"))
      (node (ref "R43") (pin "2") (pinfunction "2_2") (pintype "passive"))
    )
    (net (code "108") (name "Net-(LED5-PadA)") (class "Default")
      (node (ref "LED5") (pin "A") (pinfunction "A_A") (pintype "passive"))
      (node (ref "R49") (pin "1") (pinfunction "1_1") (pintype "passive"))
    )
    (net (code "109") (name "Net-(LED6-PadA)") (class "Default")
      (node (ref "LED6") (pin "A") (pinfunction "A_A") (pintype "passive"))
      (node (ref "R52") (pin "2") (pinfunction "2_2") (pintype "passive"))
    )
    (net (code "110") (name "Net-(LED7-PadA)") (class "Default")
      (node (ref "LED7") (pin "A") (pinfunction "A_A") (pintype "passive"))
      (node (ref "R39") (pin "1") (pinfunction "1_1") (pintype "passive"))
    )
    (net (code "111") (name "Net-(P2-Pad1)") (class "Default")
      (node (ref "P2") (pin "1") (pinfunction "1_1") (pintype "passive"))
      (node (ref "U$13") (pin "1") (pinfunction "1_1") (pintype "bidirectional"))
      (node (ref "U$13") (pin "2") (pinfunction "1_2") (pintype "bidirectional"))
    )
    (net (code "112") (name "Net-(P3-Pad1)") (class "Default")
      (node (ref "P3") (pin "1") (pinfunction "1_1") (pintype "passive"))
      (node (ref "U$13") (pin "3") (pinfunction "2_3") (pintype "bidirectional"))
      (node (ref "U$13") (pin "4") (pinfunction "2_4") (pintype "bidirectional"))
    )
    (net (code "113") (name "Net-(P4-Pad1)") (class "Default")
      (node (ref "P4") (pin "1") (pinfunction "1_1") (pintype "passive"))
      (node (ref "U$2") (pin "1") (pinfunction "1_1") (pintype "bidirectional"))
    )
    (net (code "114") (name "Net-(P5-Pad1)") (class "Default")
      (node (ref "P5") (pin "1") (pinfunction "1_1") (pintype "passive"))
      (node (ref "U$2") (pin "2") (pinfunction "2_2") (pintype "bidirectional"))
    )
    (net (code "115") (name "Net-(P7-Pad1)") (class "Default")
      (node (ref "P7") (pin "1") (pinfunction "1_1") (pintype "passive"))
      (node (ref "U$3") (pin "2") (pinfunction "2_2") (pintype "bidirectional"))
    )
    (net (code "116") (name "Net-(Q1-D)") (class "Default")
      (node (ref "H13") (pin "2") (pinfunction "2_2") (pintype "passive"))
      (node (ref "LED1") (pin "C") (pinfunction "C_C") (pintype "passive"))
      (node (ref "Q1") (pin "3") (pinfunction "D_3") (pintype "passive"))
    )
    (net (code "117") (name "Net-(Q1-G)") (class "Default")
      (node (ref "Q1") (pin "1") (pinfunction "G_1") (pintype "passive"))
      (node (ref "R35") (pin "1") (pinfunction "1_1") (pintype "passive"))
      (node (ref "R36") (pin "1") (pinfunction "1_1") (pintype "passive"))
    )
    (net (code "118") (name "Net-(Q2-D)") (class "Default")
      (node (ref "H14") (pin "2") (pinfunction "2_2") (pintype "passive"))
      (node (ref "LED2") (pin "C") (pinfunction "C_C") (pintype "passive"))
      (node (ref "Q2") (pin "3") (pinfunction "D_3") (pintype "passive"))
    )
    (net (code "119") (name "Net-(Q2-G)") (class "Default")
      (node (ref "Q2") (pin "1") (pinfunction "G_1") (pintype "passive"))
      (node (ref "R27") (pin "1") (pinfunction "1_1") (pintype "passive"))
      (node (ref "R37") (pin "1") (pinfunction "1_1") (pintype "passive"))
    )
    (net (code "120") (name "Net-(Q3-D)") (class "Default")
      (node (ref "H15") (pin "2") (pinfunction "2_2") (pintype "passive"))
      (node (ref "LED3") (pin "C") (pinfunction "C_C") (pintype "passive"))
      (node (ref "Q3") (pin "3") (pinfunction "D_3") (pintype "passive"))
    )
    (net (code "121") (name "Net-(Q3-G)") (class "Default")
      (node (ref "Q3") (pin "1") (pinfunction "G_1") (pintype "passive"))
      (node (ref "R40") (pin "1") (pinfunction "1_1") (pintype "passive"))
      (node (ref "R41") (pin "1") (pinfunction "1_1") (pintype "passive"))
    )
    (net (code "122") (name "Net-(STEPSTICK-X-RST)") (class "Default")
      (node (ref "STEPSTICK-X") (pin "RESET") (pinfunction "RST_RESET") (pintype "bidirectional"))
      (node (ref "STEPSTICK-X") (pin "SLEEP") (pinfunction "SLP_SLEEP") (pintype "bidirectional"))
    )
    (net (code "123") (name "Net-(STEPSTICK-Y-RST)") (class "Default")
      (node (ref "STEPSTICK-Y") (pin "RESET") (pinfunction "RST_RESET") (pintype "bidirectional"))
      (node (ref "STEPSTICK-Y") (pin "SLEEP") (pinfunction "SLP_SLEEP") (pintype "bidirectional"))
    )
    (net (code "124") (name "Net-(STEPSTICK-Z1-RST)") (class "Default")
      (node (ref "STEPSTICK-Z1") (pin "RESET") (pinfunction "RST_RESET") (pintype "bidirectional"))
      (node (ref "STEPSTICK-Z1") (pin "SLEEP") (pinfunction "SLP_SLEEP") (pintype "bidirectional"))
    )
    (net (code "125") (name "Net-(STEPSTICK-Z2-RST)") (class "Default")
      (node (ref "STEPSTICK-Z2") (pin "RESET") (pinfunction "RST_RESET") (pintype "bidirectional"))
      (node (ref "STEPSTICK-Z2") (pin "SLEEP") (pinfunction "SLP_SLEEP") (pintype "bidirectional"))
    )
    (net (code "126") (name "PSON") (class "Default")
      (node (ref "JP27") (pin "1") (pinfunction "1_1") (pintype "passive"))
      (node (ref "U$1") (pin "40") (pinfunction "40_40") (pintype "bidirectional"))
    )
    (net (code "127") (name "PWM1") (class "Default")
      (node (ref "JP25") (pin "1") (pinfunction "1_1") (pintype "passive"))
      (node (ref "U$1") (pin "5") (pinfunction "5_5") (pintype "bidirectional"))
    )
    (net (code "128") (name "PWM2") (class "Default")
      (node (ref "JP20") (pin "1") (pinfunction "1_1") (pintype "passive"))
      (node (ref "U$1") (pin "6") (pinfunction "6_6") (pintype "bidirectional"))
    )
    (net (code "129") (name "PWM3") (class "Default")
      (node (ref "JP19") (pin "1") (pinfunction "1_1") (pintype "passive"))
    )
    (net (code "130") (name "RESET") (class "Default")
      (node (ref "H21") (pin "2") (pinfunction "2_2") (pintype "passive"))
      (node (ref "RESET") (pin "1") (pinfunction "1_1") (pintype "bidirectional"))
      (node (ref "SV5") (pin "7") (pinfunction "7_7") (pintype "passive"))
      (node (ref "U$1") (pin "RESET_ICSP") (pinfunction "RESET_ICSP_RESET_ICSP") (pintype "bidirectional"))
    )
    (net (code "131") (name "RX0") (class "Default")
      (node (ref "JP16") (pin "1") (pinfunction "1_1") (pintype "passive"))
      (node (ref "U$1") (pin "RX0") (pinfunction "RX0_RX0") (pintype "bidirectional"))
    )
    (net (code "132") (name "RX1") (class "Default")
      (node (ref "JP18") (pin "1") (pinfunction "1_1") (pintype "passive"))
      (node (ref "U$1") (pin "RX1") (pinfunction "RX1_RX1") (pintype "bidirectional"))
    )
    (net (code "133") (name "SCK") (class "Default")
      (node (ref "SV5") (pin "1") (pinfunction "1_1") (pintype "passive"))
      (node (ref "U$1") (pin "SCK_ICSP") (pinfunction "SCK_ICSP_SCK_ICSP") (pintype "bidirectional"))
    )
    (net (code "134") (name "SCL") (class "Default")
      (node (ref "H16") (pin "4") (pinfunction "4_4") (pintype "passive"))
      (node (ref "IC2") (pin "6") (pinfunction "SCL_6") (pintype "input"))
      (node (ref "U$1") (pin "SCL") (pinfunction "SCL_SCL") (pintype "bidirectional"))
    )
    (net (code "135") (name "SCL1") (class "Default")
      (node (ref "JP6") (pin "1") (pinfunction "1_1") (pintype "passive"))
      (node (ref "U$1") (pin "SCL1") (pinfunction "SCL1_SCL1") (pintype "bidirectional"))
    )
    (net (code "136") (name "SDA") (class "Default")
      (node (ref "H16") (pin "3") (pinfunction "3_3") (pintype "passive"))
      (node (ref "IC2") (pin "5") (pinfunction "SDA_5") (pintype "bidirectional"))
      (node (ref "U$1") (pin "SDA") (pinfunction "SDA_SDA") (pintype "bidirectional"))
    )
    (net (code "137") (name "SDA1") (class "Default")
      (node (ref "JP14") (pin "1") (pinfunction "1_1") (pintype "passive"))
      (node (ref "U$1") (pin "SDA1") (pinfunction "SDA1_SDA1") (pintype "bidirectional"))
    )
    (net (code "138") (name "TX0") (class "Default")
      (node (ref "JP15") (pin "1") (pinfunction "1_1") (pintype "passive"))
      (node (ref "U$1") (pin "TX0") (pinfunction "TX0_TX0") (pintype "bidirectional"))
    )
    (net (code "139") (name "TX1") (class "Default")
      (node (ref "JP17") (pin "1") (pinfunction "1_1") (pintype "passive"))
      (node (ref "U$1") (pin "TX1") (pinfunction "TX1_TX1") (pintype "bidirectional"))
    )
    (net (code "140") (name "X-DIR") (class "Default")
      (node (ref "STEPSTICK-X") (pin "DIR") (pinfunction "DIR_DIR") (pintype "bidirectional"))
      (node (ref "U$1") (pin "TX2") (pinfunction "TX2_TX2") (pintype "bidirectional"))
    )
    (net (code "141") (name "X-ENA") (class "Default")
      (node (ref "R3") (pin "2") (pinfunction "2_2") (pintype "passive"))
      (node (ref "STEPSTICK-X") (pin "ENABLE") (pinfunction "EN_ENABLE") (pintype "bidirectional"))
      (node (ref "U$1") (pin "22") (pinfunction "22_22") (pintype "bidirectional"))
    )
    (net (code "142") (name "X-MIN") (class "Default")
      (node (ref "C51") (pin "2") (pinfunction "2_2") (pintype "passive"))
      (node (ref "R16") (pin "1") (pinfunction "1_1") (pintype "passive"))
      (node (ref "U$1") (pin "38") (pinfunction "38_38") (pintype "bidirectional"))
    )
    (net (code "143") (name "X-STP") (class "Default")
      (node (ref "STEPSTICK-X") (pin "STP") (pinfunction "STEP_STP") (pintype "bidirectional"))
      (node (ref "U$1") (pin "RX2") (pinfunction "RX2_RX2") (pintype "bidirectional"))
    )
    (net (code "144") (name "Y-DIR") (class "Default")
      (node (ref "STEPSTICK-Y") (pin "DIR") (pinfunction "DIR_DIR") (pintype "bidirectional"))
      (node (ref "U$1") (pin "3") (pinfunction "3_3") (pintype "bidirectional"))
    )
    (net (code "145") (name "Y-ENA") (class "Default")
      (node (ref "R1") (pin "2") (pinfunction "2_2") (pintype "passive"))
      (node (ref "STEPSTICK-Y") (pin "ENABLE") (pinfunction "EN_ENABLE") (pintype "bidirectional"))
      (node (ref "U$1") (pin "26") (pinfunction "26_26") (pintype "bidirectional"))
    )
    (net (code "146") (name "Y-MIN") (class "Default")
      (node (ref "C49") (pin "2") (pinfunction "2_2") (pintype "passive"))
      (node (ref "R18") (pin "1") (pinfunction "1_1") (pintype "passive"))
      (node (ref "U$1") (pin "34") (pinfunction "34_34") (pintype "bidirectional"))
    )
    (net (code "147") (name "Y-STP") (class "Default")
      (node (ref "STEPSTICK-Y") (pin "STP") (pinfunction "STEP_STP") (pintype "bidirectional"))
      (node (ref "U$1") (pin "2") (pinfunction "2_2") (pintype "bidirectional"))
    )
    (net (code "148") (name "Z-DIR") (class "Default")
      (node (ref "STEPSTICK-Z1") (pin "DIR") (pinfunction "DIR_DIR") (pintype "bidirectional"))
      (node (ref "U$1") (pin "A9") (pinfunction "A9_A9") (pintype "bidirectional"))
    )
    (net (code "149") (name "Z-ENA") (class "Default")
      (node (ref "R5") (pin "2") (pinfunction "2_2") (pintype "passive"))
      (node (ref "STEPSTICK-Z1") (pin "ENABLE") (pinfunction "EN_ENABLE") (pintype "bidirectional"))
      (node (ref "U$1") (pin "RX3") (pinfunction "RX3_RX3") (pintype "bidirectional"))
    )
    (net (code "150") (name "Z-MIN") (class "Default")
      (node (ref "C32") (pin "2") (pinfunction "2_2") (pintype "passive"))
      (node (ref "R20") (pin "1") (pinfunction "1_1") (pintype "passive"))
      (node (ref "U$1") (pin "30") (pinfunction "30_30") (pintype "bidirectional"))
    )
    (net (code "151") (name "Z-STP") (class "Default")
      (node (ref "STEPSTICK-Z1") (pin "STP") (pinfunction "STEP_STP") (pintype "bidirectional"))
      (node (ref "U$1") (pin "A10") (pinfunction "A10_A10") (pintype "bidirectional"))
    )
    (net (code "152") (name "unconnected-(JP7-Pad1)") (class "Default")
      (node (ref "JP7") (pin "1") (pinfunction "1_1") (pintype "passive"))
    )
    (net (code "153") (name "unconnected-(SV5-Pad9)") (class "Default")
      (node (ref "SV5") (pin "9") (pinfunction "9_9") (pintype "passive"))
    )
    (net (code "154") (name "unconnected-(U$1-Pad5V)") (class "Default")
      (node (ref "U$1") (pin "5V") (pinfunction "5V_5V") (pintype "bidirectional"))
    )
    (net (code "155") (name "unconnected-(U$1-PadAREF)") (class "Default")
      (node (ref "U$1") (pin "AREF") (pinfunction "AREF_AREF") (pintype "bidirectional"))
    )
    (net (code "156") (name "unconnected-(U$1-PadGND1)") (class "Default")
      (node (ref "U$1") (pin "GND1") (pinfunction "GND1_GND1") (pintype "bidirectional"))
    )
    (net (code "157") (name "unconnected-(U$1-PadNC)") (class "Default")
      (node (ref "U$1") (pin "NC") (pinfunction "NC_NC") (pintype "bidirectional"))
    )
    (net (code "158") (name "unconnected-(U$1-PadRESET)") (class "Default")
      (node (ref "U$1") (pin "RESET") (pinfunction "RESET_RESET") (pintype "bidirectional"))
    )
    (net (code "159") (name "unconnected-(X1B-S-Pad2)") (class "Default")
      (node (ref "X1") (pin "2") (pinfunction "S_2") (pintype "passive"))
    )
  )
)
